# OpenPneu_ver2.net
KiCad netlist of a schematic drawn in EAGLE
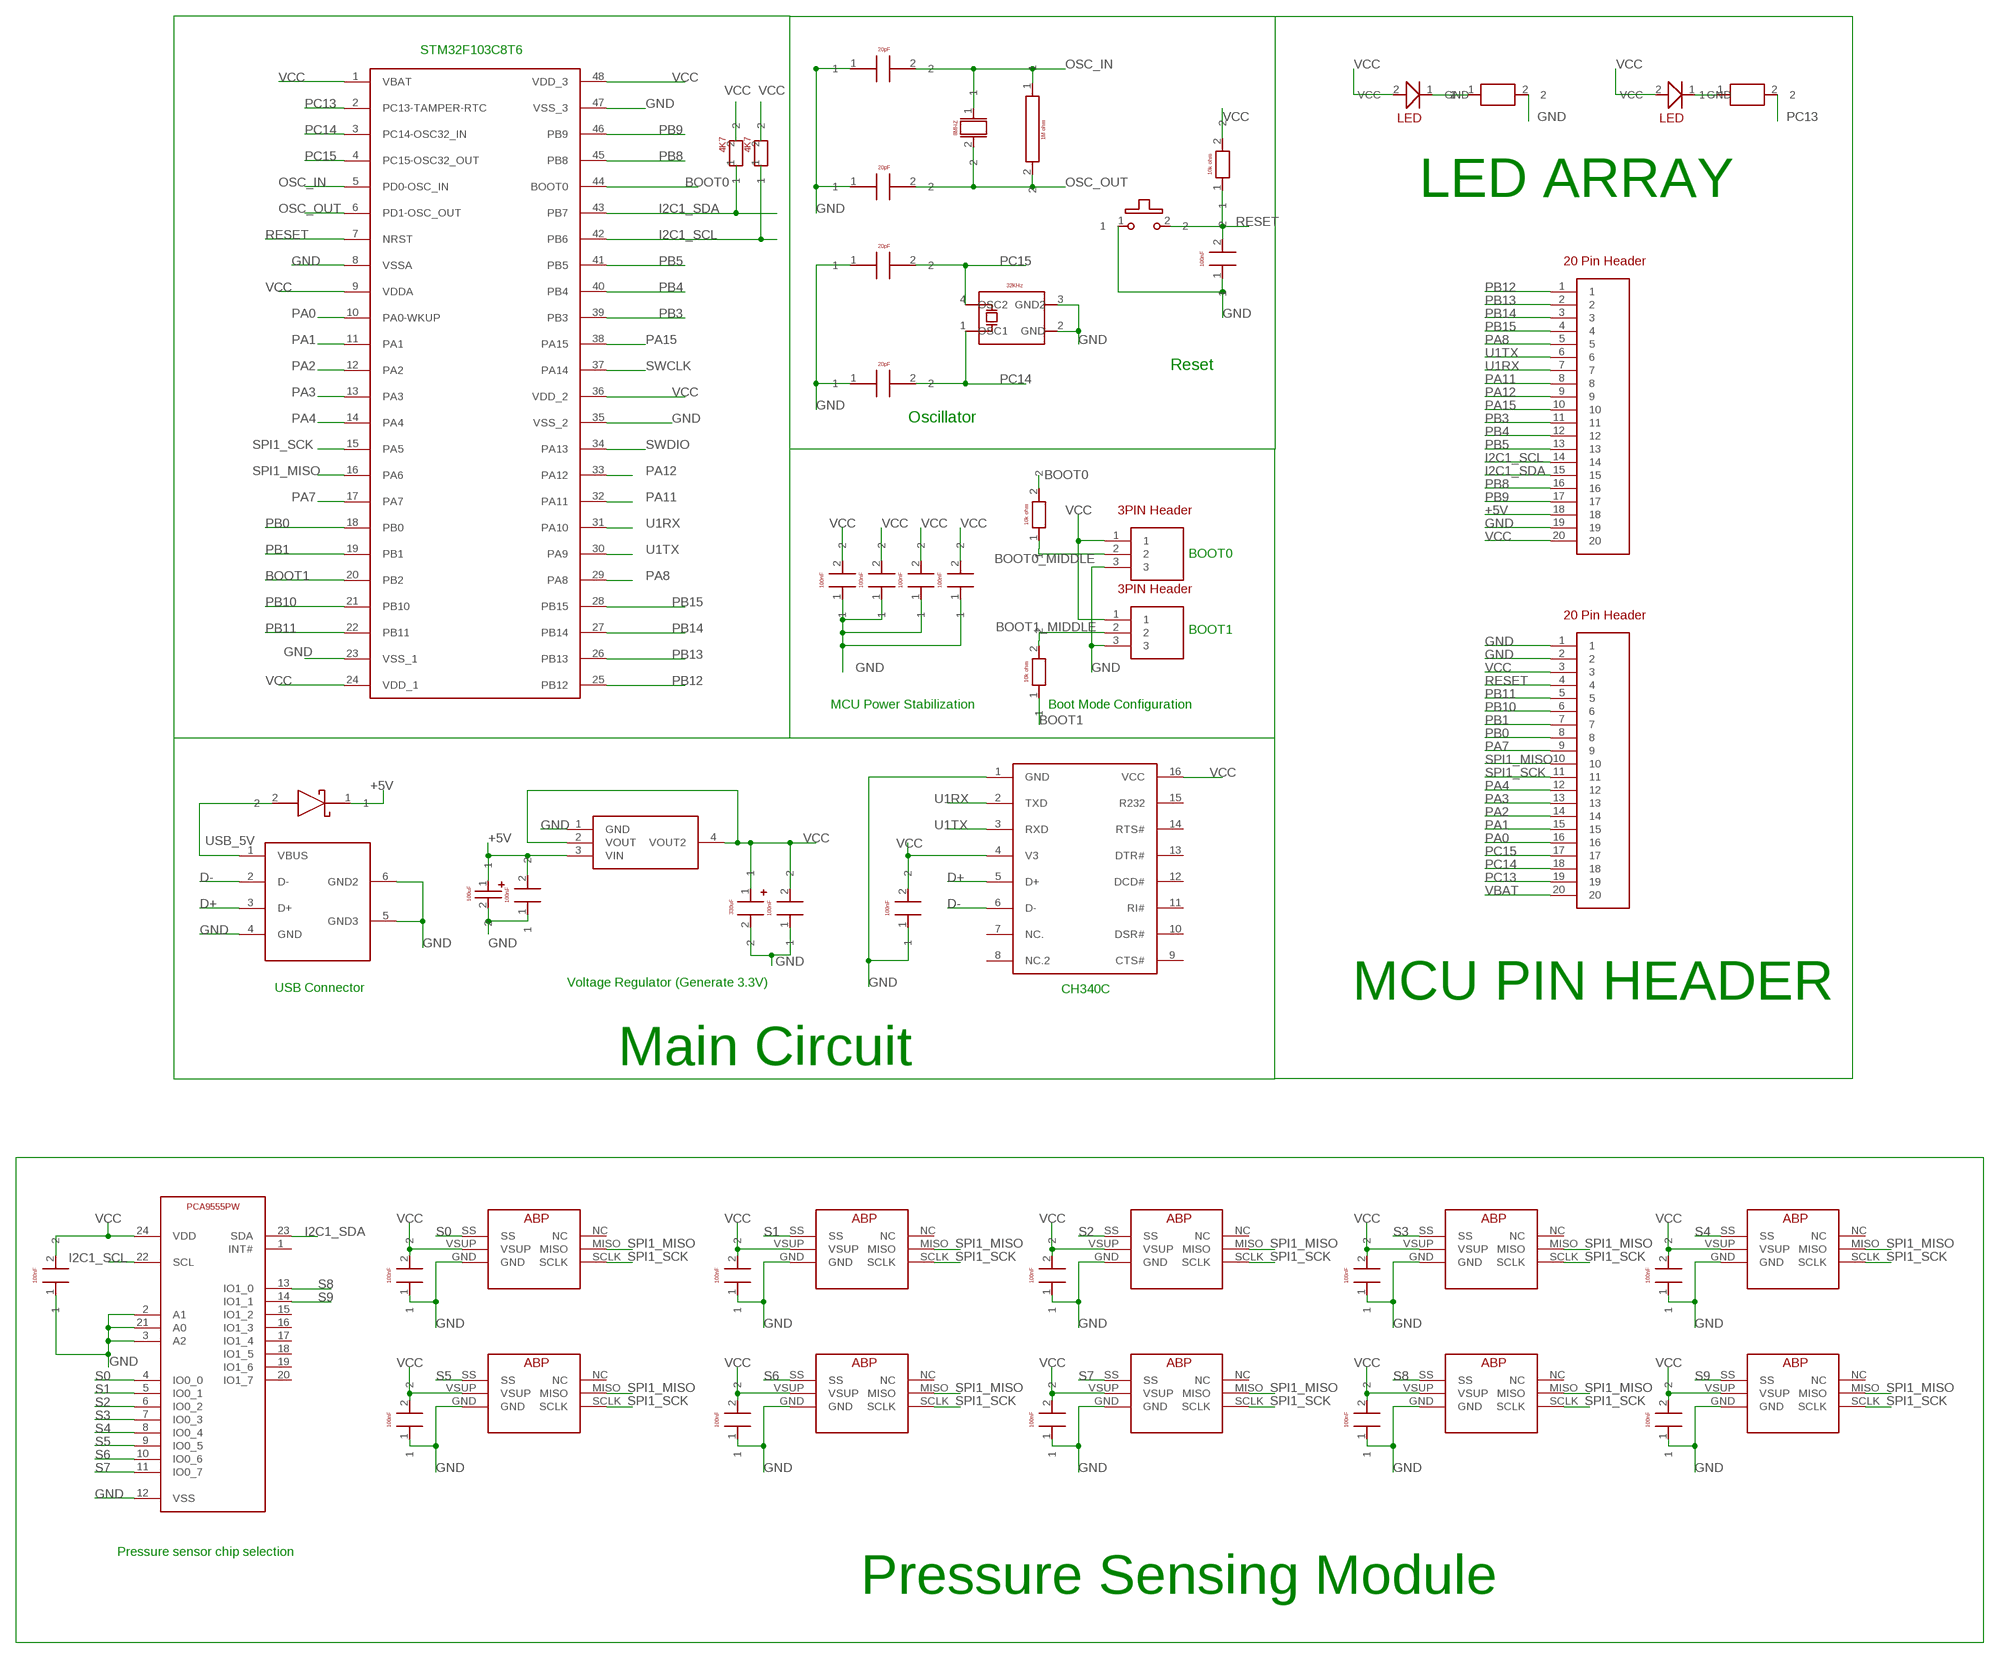
[diagram p0: schematic, sheet 1, part 1 of 3]
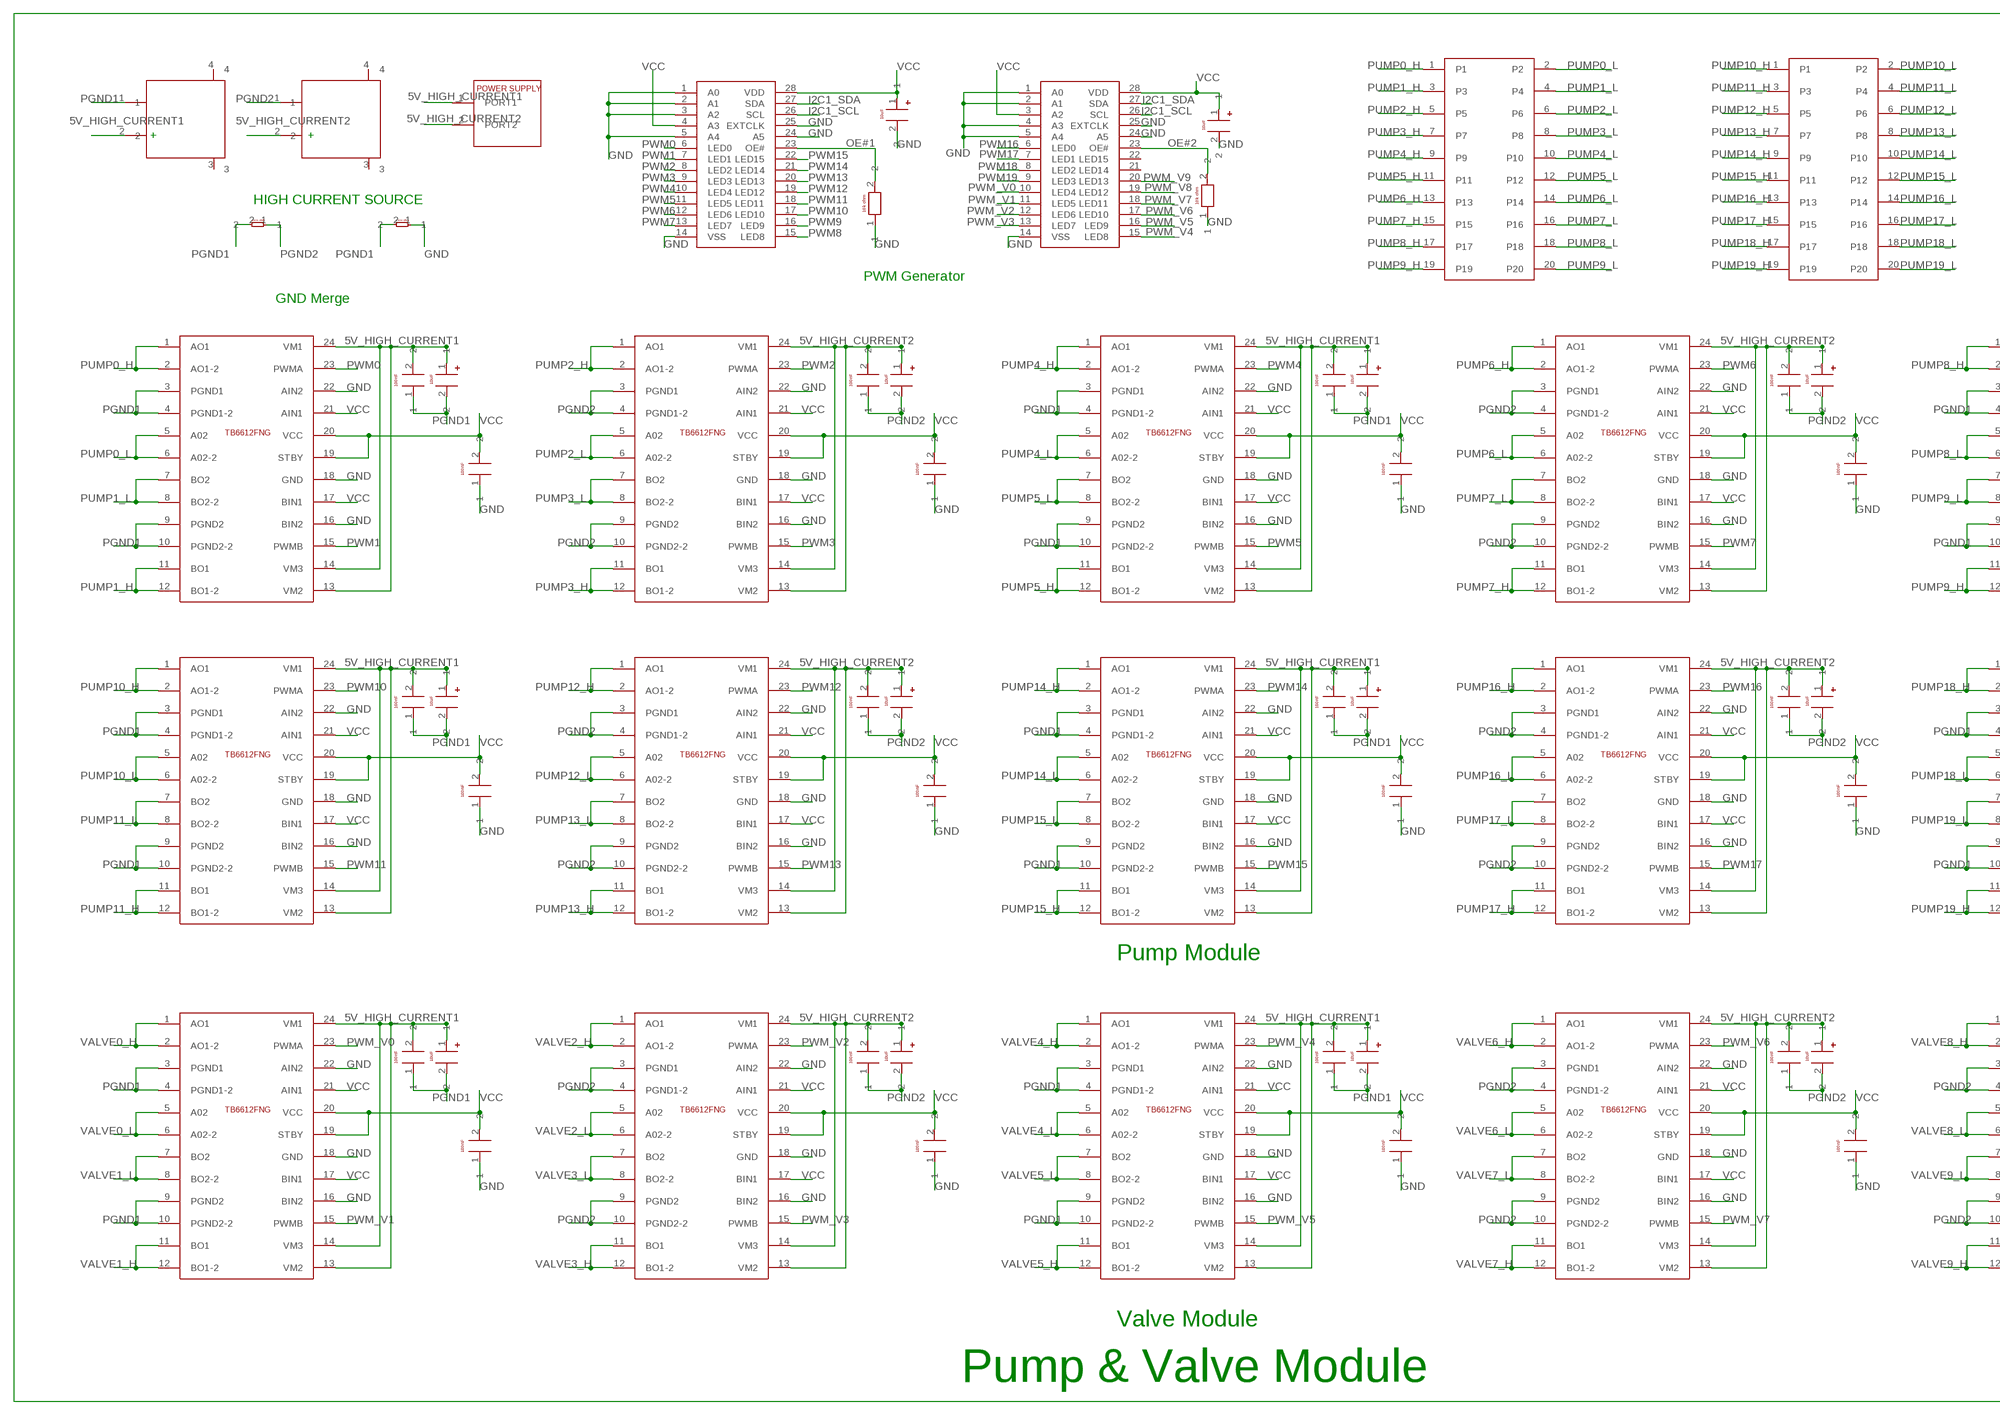
[diagram p1: schematic, sheet 1, part 2 of 3]
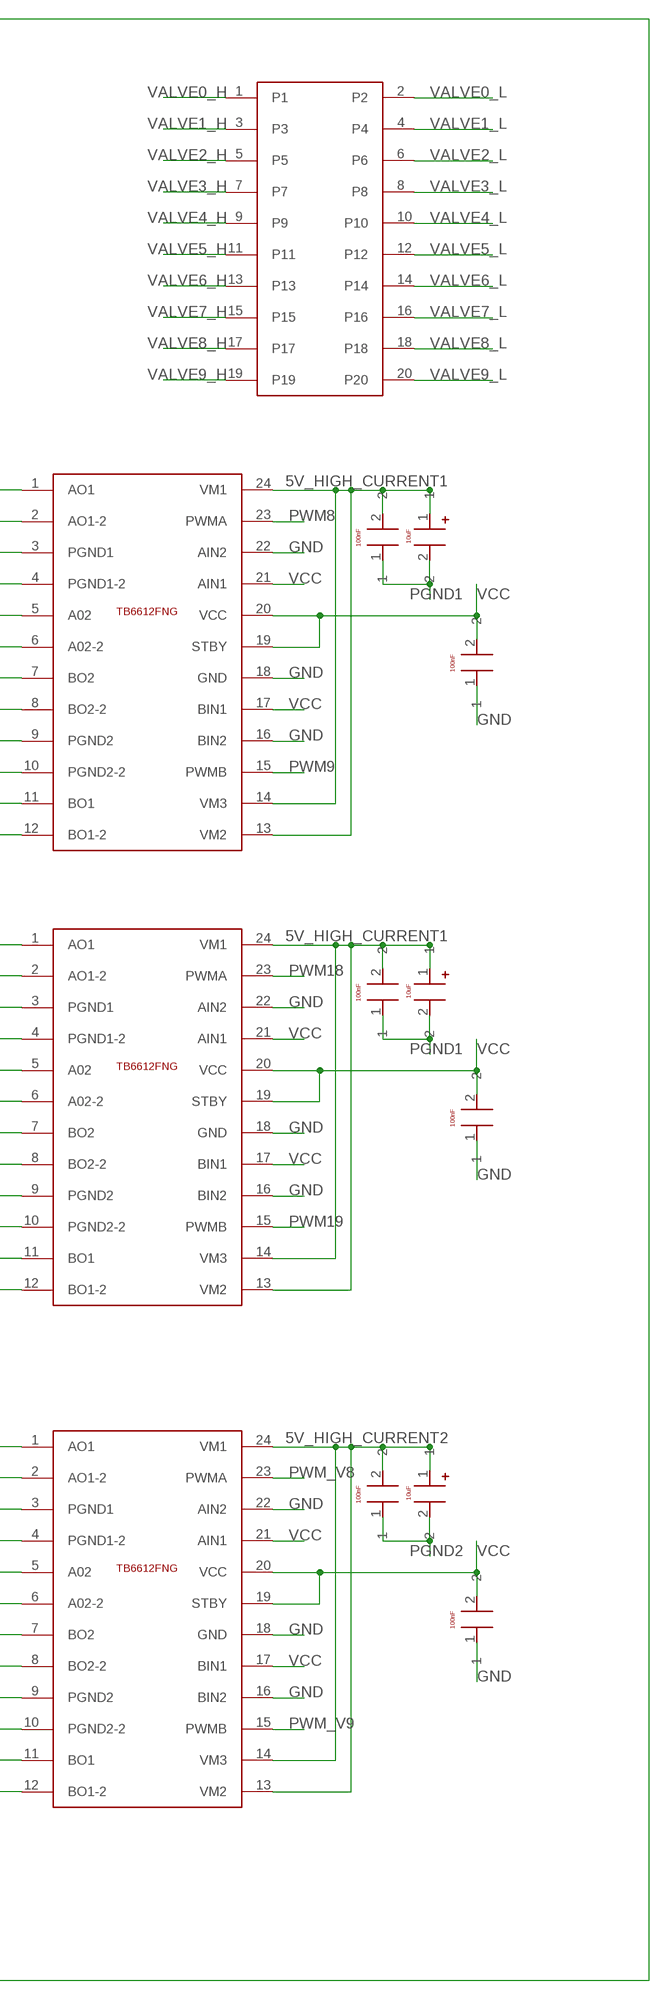
[diagram p2: schematic, sheet 1, part 3 of 3]

(export (version "E")
  (design (tool "Eeschema 10.0.6"))
  (components
    (comp (ref "J1")
      (value "D01-9922046")
      (footprint "eagle-import:HDRV20W46P0X254_1X20_5090X254X")
      (fields (field (name "RS_PART_NUMBER") "5473302"))
      (libsource (lib "eagle-import") (part "D01-9922046"))
    )
    (comp (ref "J2")
      (value "D01-9922046")
      (footprint "eagle-import:HDRV20W46P0X254_1X20_5090X254X")
      (fields (field (name "RS_PART_NUMBER") "5473302"))
      (libsource (lib "eagle-import") (part "D01-9922046"))
    )
    (comp (ref "U$1")
      (value "STM32F103_DEVICE")
      (footprint "eagle-import:LQFP-48_L7.0-W7.0-P0.50-LS9.27PRIMARY")
      (libsource (lib "eagle-import") (part "STM32F103_DEVICE"))
    )
    (comp (ref "U$2")
      (value "8MHZ_DEVICE")
      (footprint "eagle-import:CRYSTAL-SMD_L11.5-W4.8-LS12.A9PRIMARY")
      (libsource (lib "eagle-import") (part "8MHZ_DEVICE"))
    )
    (comp (ref "U$3")
      (value "20PF_DEVICE")
      (footprint "eagle-import:C0603_1PRIMARY")
      (libsource (lib "eagle-import") (part "20PF_DEVICE"))
    )
    (comp (ref "U$4")
      (value "20PF_DEVICE")
      (footprint "eagle-import:C0603_1PRIMARY")
      (libsource (lib "eagle-import") (part "20PF_DEVICE"))
    )
    (comp (ref "U$5")
      (value "1M_DEVICE")
      (footprint "eagle-import:R0603_1PRIMARY")
      (libsource (lib "eagle-import") (part "1M_DEVICE"))
    )
    (comp (ref "U$6")
      (value "32KHZ_DEVICE")
      (footprint "eagle-import:MC-306_4P-L8.0-W3.2-P5.5-BL_1PRIMARY")
      (libsource (lib "eagle-import") (part "32KHZ_DEVICE"))
    )
    (comp (ref "U$7")
      (value "20PF_DEVICE")
      (footprint "eagle-import:C0603_1PRIMARY")
      (libsource (lib "eagle-import") (part "20PF_DEVICE"))
    )
    (comp (ref "U$8")
      (value "20PF_DEVICE")
      (footprint "eagle-import:C0603_1PRIMARY")
      (libsource (lib "eagle-import") (part "20PF_DEVICE"))
    )
    (comp (ref "U$9")
      (value "VOLTAGE_REGULATOR")
      (footprint "eagle-import:SOT-223-3_L6.5-W3.4-P2.30-LS59PRIMARY")
      (libsource (lib "eagle-import") (part "VOLTAGE_REGULATOR"))
    )
    (comp (ref "U$10")
      (value "100UF")
      (footprint "eagle-import:CAP-SMD_L6.0-W3.2-R-RD_1PRIMARY")
      (libsource (lib "eagle-import") (part "100UF"))
    )
    (comp (ref "U$11")
      (value "100NF_DEVICE")
      (footprint "eagle-import:C0603_1PRIMARY")
      (libsource (lib "eagle-import") (part "100NF_DEVICE"))
    )
    (comp (ref "U$12")
      (value "330UF_DEVICE")
      (footprint "eagle-import:CAP-SMD_L6.0-W3.2-R-RD_1PRIMARY")
      (libsource (lib "eagle-import") (part "330UF_DEVICE"))
    )
    (comp (ref "U$13")
      (value "100NF_DEVICE")
      (footprint "eagle-import:C0603_1PRIMARY")
      (libsource (lib "eagle-import") (part "100NF_DEVICE"))
    )
    (comp (ref "U$14")
      (value "100NF_DEVICE")
      (footprint "eagle-import:C0603_1PRIMARY")
      (libsource (lib "eagle-import") (part "100NF_DEVICE"))
    )
    (comp (ref "U$15")
      (value "100NF_DEVICE")
      (footprint "eagle-import:C0603_1PRIMARY")
      (libsource (lib "eagle-import") (part "100NF_DEVICE"))
    )
    (comp (ref "U$16")
      (value "100NF_DEVICE")
      (footprint "eagle-import:C0603_1PRIMARY")
      (libsource (lib "eagle-import") (part "100NF_DEVICE"))
    )
    (comp (ref "U$17")
      (value "100NF_DEVICE")
      (footprint "eagle-import:C0603_1PRIMARY")
      (libsource (lib "eagle-import") (part "100NF_DEVICE"))
    )
    (comp (ref "U$18")
      (value "USB_NORM_VER2_DEV")
      (footprint "eagle-import:USB-B-TH_USB-B01_1PRIMARY")
      (libsource (lib "eagle-import") (part "USB_NORM_VER2_DEV"))
    )
    (comp (ref "U$19")
      (value "DIODE_DEVICE")
      (footprint "eagle-import:SMA_L4.4-W2.8-LS5.4-RD_1PRIMARY")
      (libsource (lib "eagle-import") (part "DIODE_DEVICE"))
    )
    (comp (ref "U$20")
      (value "CH340C_DEVICE")
      (footprint "eagle-import:SOP-16_L10.0-W3.9-P1.27-LS6.C7PRIMARY")
      (libsource (lib "eagle-import") (part "CH340C_DEVICE"))
    )
    (comp (ref "U$21")
      (value "100NF_DEVICE")
      (footprint "eagle-import:C0603_1PRIMARY")
      (libsource (lib "eagle-import") (part "100NF_DEVICE"))
    )
    (comp (ref "U$22")
      (value "3PIN_DEVICE")
      (footprint "eagle-import:HDRV20W46P0X254_1X20_5090X254X")
      (libsource (lib "eagle-import") (part "3PIN_DEVICE"))
    )
    (comp (ref "U$23")
      (value "3PIN_DEVICE")
      (footprint "eagle-import:HDRV20W46P0X254_1X20_5090X254X")
      (libsource (lib "eagle-import") (part "3PIN_DEVICE"))
    )
    (comp (ref "U$24")
      (value "10K_DEVICE")
      (footprint "eagle-import:R0603_1PRIMARY")
      (libsource (lib "eagle-import") (part "10K_DEVICE"))
    )
    (comp (ref "U$25")
      (value "10K_DEVICE")
      (footprint "eagle-import:R0603_1PRIMARY")
      (libsource (lib "eagle-import") (part "10K_DEVICE"))
    )
    (comp (ref "U$26")
      (value "BUTTON_DEVICE")
      (footprint "eagle-import:SW-SMD_SMK_JPM1040-XXXXFC_1PRIMARY")
      (libsource (lib "eagle-import") (part "BUTTON_DEVICE"))
    )
    (comp (ref "U$27")
      (value "POWER")
      (footprint "eagle-import:CONN-TH_P5.00_KF301-5.0-2P_1PRIMARY")
      (libsource (lib "eagle-import") (part "POWER"))
    )
    (comp (ref "U$28")
      (value "10K_DEVICE")
      (footprint "eagle-import:R0603_1PRIMARY")
      (libsource (lib "eagle-import") (part "10K_DEVICE"))
    )
    (comp (ref "U$29")
      (value "PCA9685PCA9685")
      (footprint "eagle-import:TSSOP-28_L9.7-W4.4-P0.65-LS6FFPRIMARY")
      (libsource (lib "eagle-import") (part "PCA9685PCA9685"))
    )
    (comp (ref "U$30")
      (value "PCA9685PCA9685")
      (footprint "eagle-import:TSSOP-28_L9.7-W4.4-P0.65-LS6FFPRIMARY")
      (libsource (lib "eagle-import") (part "PCA9685PCA9685"))
    )
    (comp (ref "U$31")
      (value "10K_DEVICE")
      (footprint "eagle-import:R0603_1PRIMARY")
      (libsource (lib "eagle-import") (part "10K_DEVICE"))
    )
    (comp (ref "U$32")
      (value "10UF_DEVICE")
      (footprint "eagle-import:CAP-SMD_L3.5-W2.8-R-RD_1PRIMARY")
      (libsource (lib "eagle-import") (part "10UF_DEVICE"))
    )
    (comp (ref "U$33")
      (value "10UF_DEVICE")
      (footprint "eagle-import:CAP-SMD_L3.5-W2.8-R-RD_1PRIMARY")
      (libsource (lib "eagle-import") (part "10UF_DEVICE"))
    )
    (comp (ref "U$34")
      (value "10K_DEVICE")
      (footprint "eagle-import:R0603_1PRIMARY")
      (libsource (lib "eagle-import") (part "10K_DEVICE"))
    )
    (comp (ref "U$35")
      (value "TB6612FNG")
      (footprint "eagle-import:SSOP-24_L8.3-W5.6-P0.65-LS7.93PRIMARY")
      (libsource (lib "eagle-import") (part "TB6612FNG"))
    )
    (comp (ref "U$36")
      (value "TB6612FNG")
      (footprint "eagle-import:SSOP-24_L8.3-W5.6-P0.65-LS7.93PRIMARY")
      (libsource (lib "eagle-import") (part "TB6612FNG"))
    )
    (comp (ref "U$37")
      (value "100NF_DEVICE")
      (footprint "eagle-import:C0603_1PRIMARY")
      (libsource (lib "eagle-import") (part "100NF_DEVICE"))
    )
    (comp (ref "U$38")
      (value "10UF_DEVICE")
      (footprint "eagle-import:CAP-SMD_L3.5-W2.8-R-RD_1PRIMARY")
      (libsource (lib "eagle-import") (part "10UF_DEVICE"))
    )
    (comp (ref "U$39")
      (value "100NF_DEVICE")
      (footprint "eagle-import:C0603_1PRIMARY")
      (libsource (lib "eagle-import") (part "100NF_DEVICE"))
    )
    (comp (ref "U$40")
      (value "100NF_DEVICE")
      (footprint "eagle-import:C0603_1PRIMARY")
      (libsource (lib "eagle-import") (part "100NF_DEVICE"))
    )
    (comp (ref "U$41")
      (value "10UF_DEVICE")
      (footprint "eagle-import:CAP-SMD_L3.5-W2.8-R-RD_1PRIMARY")
      (libsource (lib "eagle-import") (part "10UF_DEVICE"))
    )
    (comp (ref "U$42")
      (value "100NF_DEVICE")
      (footprint "eagle-import:C0603_1PRIMARY")
      (libsource (lib "eagle-import") (part "100NF_DEVICE"))
    )
    (comp (ref "U$43")
      (value "TB6612FNG")
      (footprint "eagle-import:SSOP-24_L8.3-W5.6-P0.65-LS7.93PRIMARY")
      (libsource (lib "eagle-import") (part "TB6612FNG"))
    )
    (comp (ref "U$44")
      (value "100NF_DEVICE")
      (footprint "eagle-import:C0603_1PRIMARY")
      (libsource (lib "eagle-import") (part "100NF_DEVICE"))
    )
    (comp (ref "U$45")
      (value "10UF_DEVICE")
      (footprint "eagle-import:CAP-SMD_L3.5-W2.8-R-RD_1PRIMARY")
      (libsource (lib "eagle-import") (part "10UF_DEVICE"))
    )
    (comp (ref "U$46")
      (value "100NF_DEVICE")
      (footprint "eagle-import:C0603_1PRIMARY")
      (libsource (lib "eagle-import") (part "100NF_DEVICE"))
    )
    (comp (ref "U$47")
      (value "TB6612FNG")
      (footprint "eagle-import:SSOP-24_L8.3-W5.6-P0.65-LS7.93PRIMARY")
      (libsource (lib "eagle-import") (part "TB6612FNG"))
    )
    (comp (ref "U$48")
      (value "100NF_DEVICE")
      (footprint "eagle-import:C0603_1PRIMARY")
      (libsource (lib "eagle-import") (part "100NF_DEVICE"))
    )
    (comp (ref "U$49")
      (value "10UF_DEVICE")
      (footprint "eagle-import:CAP-SMD_L3.5-W2.8-R-RD_1PRIMARY")
      (libsource (lib "eagle-import") (part "10UF_DEVICE"))
    )
    (comp (ref "U$50")
      (value "100NF_DEVICE")
      (footprint "eagle-import:C0603_1PRIMARY")
      (libsource (lib "eagle-import") (part "100NF_DEVICE"))
    )
    (comp (ref "U$51")
      (value "TB6612FNG")
      (footprint "eagle-import:SSOP-24_L8.3-W5.6-P0.65-LS7.93PRIMARY")
      (libsource (lib "eagle-import") (part "TB6612FNG"))
    )
    (comp (ref "U$52")
      (value "100NF_DEVICE")
      (footprint "eagle-import:C0603_1PRIMARY")
      (libsource (lib "eagle-import") (part "100NF_DEVICE"))
    )
    (comp (ref "U$53")
      (value "10UF_DEVICE")
      (footprint "eagle-import:CAP-SMD_L3.5-W2.8-R-RD_1PRIMARY")
      (libsource (lib "eagle-import") (part "10UF_DEVICE"))
    )
    (comp (ref "U$54")
      (value "100NF_DEVICE")
      (footprint "eagle-import:C0603_1PRIMARY")
      (libsource (lib "eagle-import") (part "100NF_DEVICE"))
    )
    (comp (ref "U$55")
      (value "TB6612FNG")
      (footprint "eagle-import:SSOP-24_L8.3-W5.6-P0.65-LS7.93PRIMARY")
      (libsource (lib "eagle-import") (part "TB6612FNG"))
    )
    (comp (ref "U$56")
      (value "100NF_DEVICE")
      (footprint "eagle-import:C0603_1PRIMARY")
      (libsource (lib "eagle-import") (part "100NF_DEVICE"))
    )
    (comp (ref "U$57")
      (value "10UF_DEVICE")
      (footprint "eagle-import:CAP-SMD_L3.5-W2.8-R-RD_1PRIMARY")
      (libsource (lib "eagle-import") (part "10UF_DEVICE"))
    )
    (comp (ref "U$58")
      (value "100NF_DEVICE")
      (footprint "eagle-import:C0603_1PRIMARY")
      (libsource (lib "eagle-import") (part "100NF_DEVICE"))
    )
    (comp (ref "U$59")
      (value "TB6612FNG")
      (footprint "eagle-import:SSOP-24_L8.3-W5.6-P0.65-LS7.93PRIMARY")
      (libsource (lib "eagle-import") (part "TB6612FNG"))
    )
    (comp (ref "U$60")
      (value "100NF_DEVICE")
      (footprint "eagle-import:C0603_1PRIMARY")
      (libsource (lib "eagle-import") (part "100NF_DEVICE"))
    )
    (comp (ref "U$61")
      (value "10UF_DEVICE")
      (footprint "eagle-import:CAP-SMD_L3.5-W2.8-R-RD_1PRIMARY")
      (libsource (lib "eagle-import") (part "10UF_DEVICE"))
    )
    (comp (ref "U$62")
      (value "100NF_DEVICE")
      (footprint "eagle-import:C0603_1PRIMARY")
      (libsource (lib "eagle-import") (part "100NF_DEVICE"))
    )
    (comp (ref "U$63")
      (value "TB6612FNG")
      (footprint "eagle-import:SSOP-24_L8.3-W5.6-P0.65-LS7.93PRIMARY")
      (libsource (lib "eagle-import") (part "TB6612FNG"))
    )
    (comp (ref "U$64")
      (value "100NF_DEVICE")
      (footprint "eagle-import:C0603_1PRIMARY")
      (libsource (lib "eagle-import") (part "100NF_DEVICE"))
    )
    (comp (ref "U$65")
      (value "10UF_DEVICE")
      (footprint "eagle-import:CAP-SMD_L3.5-W2.8-R-RD_1PRIMARY")
      (libsource (lib "eagle-import") (part "10UF_DEVICE"))
    )
    (comp (ref "U$66")
      (value "100NF_DEVICE")
      (footprint "eagle-import:C0603_1PRIMARY")
      (libsource (lib "eagle-import") (part "100NF_DEVICE"))
    )
    (comp (ref "U$67")
      (value "TB6612FNG")
      (footprint "eagle-import:SSOP-24_L8.3-W5.6-P0.65-LS7.93PRIMARY")
      (libsource (lib "eagle-import") (part "TB6612FNG"))
    )
    (comp (ref "U$68")
      (value "100NF_DEVICE")
      (footprint "eagle-import:C0603_1PRIMARY")
      (libsource (lib "eagle-import") (part "100NF_DEVICE"))
    )
    (comp (ref "U$69")
      (value "10UF_DEVICE")
      (footprint "eagle-import:CAP-SMD_L3.5-W2.8-R-RD_1PRIMARY")
      (libsource (lib "eagle-import") (part "10UF_DEVICE"))
    )
    (comp (ref "U$70")
      (value "100NF_DEVICE")
      (footprint "eagle-import:C0603_1PRIMARY")
      (libsource (lib "eagle-import") (part "100NF_DEVICE"))
    )
    (comp (ref "U$71")
      (value "TB6612FNG")
      (footprint "eagle-import:SSOP-24_L8.3-W5.6-P0.65-LS7.93PRIMARY")
      (libsource (lib "eagle-import") (part "TB6612FNG"))
    )
    (comp (ref "U$72")
      (value "100NF_DEVICE")
      (footprint "eagle-import:C0603_1PRIMARY")
      (libsource (lib "eagle-import") (part "100NF_DEVICE"))
    )
    (comp (ref "U$73")
      (value "10UF_DEVICE")
      (footprint "eagle-import:CAP-SMD_L3.5-W2.8-R-RD_1PRIMARY")
      (libsource (lib "eagle-import") (part "10UF_DEVICE"))
    )
    (comp (ref "U$74")
      (value "100NF_DEVICE")
      (footprint "eagle-import:C0603_1PRIMARY")
      (libsource (lib "eagle-import") (part "100NF_DEVICE"))
    )
    (comp (ref "U$75")
      (value "TB6612FNG")
      (footprint "eagle-import:SSOP-24_L8.3-W5.6-P0.65-LS7.93PRIMARY")
      (libsource (lib "eagle-import") (part "TB6612FNG"))
    )
    (comp (ref "U$76")
      (value "100NF_DEVICE")
      (footprint "eagle-import:C0603_1PRIMARY")
      (libsource (lib "eagle-import") (part "100NF_DEVICE"))
    )
    (comp (ref "U$77")
      (value "10UF_DEVICE")
      (footprint "eagle-import:CAP-SMD_L3.5-W2.8-R-RD_1PRIMARY")
      (libsource (lib "eagle-import") (part "10UF_DEVICE"))
    )
    (comp (ref "U$78")
      (value "100NF_DEVICE")
      (footprint "eagle-import:C0603_1PRIMARY")
      (libsource (lib "eagle-import") (part "100NF_DEVICE"))
    )
    (comp (ref "U$79")
      (value "TB6612FNG")
      (footprint "eagle-import:SSOP-24_L8.3-W5.6-P0.65-LS7.93PRIMARY")
      (libsource (lib "eagle-import") (part "TB6612FNG"))
    )
    (comp (ref "U$80")
      (value "100NF_DEVICE")
      (footprint "eagle-import:C0603_1PRIMARY")
      (libsource (lib "eagle-import") (part "100NF_DEVICE"))
    )
    (comp (ref "U$81")
      (value "10UF_DEVICE")
      (footprint "eagle-import:CAP-SMD_L3.5-W2.8-R-RD_1PRIMARY")
      (libsource (lib "eagle-import") (part "10UF_DEVICE"))
    )
    (comp (ref "U$82")
      (value "100NF_DEVICE")
      (footprint "eagle-import:C0603_1PRIMARY")
      (libsource (lib "eagle-import") (part "100NF_DEVICE"))
    )
    (comp (ref "U$83")
      (value "TB6612FNG")
      (footprint "eagle-import:SSOP-24_L8.3-W5.6-P0.65-LS7.93PRIMARY")
      (libsource (lib "eagle-import") (part "TB6612FNG"))
    )
    (comp (ref "U$84")
      (value "100NF_DEVICE")
      (footprint "eagle-import:C0603_1PRIMARY")
      (libsource (lib "eagle-import") (part "100NF_DEVICE"))
    )
    (comp (ref "U$85")
      (value "10UF_DEVICE")
      (footprint "eagle-import:CAP-SMD_L3.5-W2.8-R-RD_1PRIMARY")
      (libsource (lib "eagle-import") (part "10UF_DEVICE"))
    )
    (comp (ref "U$86")
      (value "100NF_DEVICE")
      (footprint "eagle-import:C0603_1PRIMARY")
      (libsource (lib "eagle-import") (part "100NF_DEVICE"))
    )
    (comp (ref "U$87")
      (value "TB6612FNG")
      (footprint "eagle-import:SSOP-24_L8.3-W5.6-P0.65-LS7.93PRIMARY")
      (libsource (lib "eagle-import") (part "TB6612FNG"))
    )
    (comp (ref "U$88")
      (value "100NF_DEVICE")
      (footprint "eagle-import:C0603_1PRIMARY")
      (libsource (lib "eagle-import") (part "100NF_DEVICE"))
    )
    (comp (ref "U$89")
      (value "10UF_DEVICE")
      (footprint "eagle-import:CAP-SMD_L3.5-W2.8-R-RD_1PRIMARY")
      (libsource (lib "eagle-import") (part "10UF_DEVICE"))
    )
    (comp (ref "U$90")
      (value "100NF_DEVICE")
      (footprint "eagle-import:C0603_1PRIMARY")
      (libsource (lib "eagle-import") (part "100NF_DEVICE"))
    )
    (comp (ref "U$91")
      (value "TB6612FNG")
      (footprint "eagle-import:SSOP-24_L8.3-W5.6-P0.65-LS7.93PRIMARY")
      (libsource (lib "eagle-import") (part "TB6612FNG"))
    )
    (comp (ref "U$92")
      (value "100NF_DEVICE")
      (footprint "eagle-import:C0603_1PRIMARY")
      (libsource (lib "eagle-import") (part "100NF_DEVICE"))
    )
    (comp (ref "U$93")
      (value "10UF_DEVICE")
      (footprint "eagle-import:CAP-SMD_L3.5-W2.8-R-RD_1PRIMARY")
      (libsource (lib "eagle-import") (part "10UF_DEVICE"))
    )
    (comp (ref "U$94")
      (value "100NF_DEVICE")
      (footprint "eagle-import:C0603_1PRIMARY")
      (libsource (lib "eagle-import") (part "100NF_DEVICE"))
    )
    (comp (ref "U$95")
      (value "ABPDANN1.6BGSA")
      (footprint "eagle-import:ABPDANN1.6BGSA")
      (libsource (lib "eagle-import") (part "ABPDANN1.6BGSA"))
    )
    (comp (ref "U$96")
      (value "ABPDANN1.6BGSA")
      (footprint "eagle-import:ABPDANN1.6BGSA")
      (libsource (lib "eagle-import") (part "ABPDANN1.6BGSA"))
    )
    (comp (ref "U$97")
      (value "100NF_DEVICE")
      (footprint "eagle-import:C0603_1PRIMARY")
      (libsource (lib "eagle-import") (part "100NF_DEVICE"))
    )
    (comp (ref "U$98")
      (value "100NF_DEVICE")
      (footprint "eagle-import:C0603_1PRIMARY")
      (libsource (lib "eagle-import") (part "100NF_DEVICE"))
    )
    (comp (ref "U$99")
      (value "ABPDANN1.6BGSA")
      (footprint "eagle-import:ABPDANN1.6BGSA")
      (libsource (lib "eagle-import") (part "ABPDANN1.6BGSA"))
    )
    (comp (ref "U$100")
      (value "100NF_DEVICE")
      (footprint "eagle-import:C0603_1PRIMARY")
      (libsource (lib "eagle-import") (part "100NF_DEVICE"))
    )
    (comp (ref "U$101")
      (value "ABPDANN1.6BGSA")
      (footprint "eagle-import:ABPDANN1.6BGSA")
      (libsource (lib "eagle-import") (part "ABPDANN1.6BGSA"))
    )
    (comp (ref "U$102")
      (value "100NF_DEVICE")
      (footprint "eagle-import:C0603_1PRIMARY")
      (libsource (lib "eagle-import") (part "100NF_DEVICE"))
    )
    (comp (ref "U$103")
      (value "ABPDANN1.6BGSA")
      (footprint "eagle-import:ABPDANN1.6BGSA")
      (libsource (lib "eagle-import") (part "ABPDANN1.6BGSA"))
    )
    (comp (ref "U$104")
      (value "100NF_DEVICE")
      (footprint "eagle-import:C0603_1PRIMARY")
      (libsource (lib "eagle-import") (part "100NF_DEVICE"))
    )
    (comp (ref "U$105")
      (value "ABPDANN1.6BGSA")
      (footprint "eagle-import:ABPDANN1.6BGSA")
      (libsource (lib "eagle-import") (part "ABPDANN1.6BGSA"))
    )
    (comp (ref "U$106")
      (value "100NF_DEVICE")
      (footprint "eagle-import:C0603_1PRIMARY")
      (libsource (lib "eagle-import") (part "100NF_DEVICE"))
    )
    (comp (ref "U$107")
      (value "ABPDANN1.6BGSA")
      (footprint "eagle-import:ABPDANN1.6BGSA")
      (libsource (lib "eagle-import") (part "ABPDANN1.6BGSA"))
    )
    (comp (ref "U$108")
      (value "100NF_DEVICE")
      (footprint "eagle-import:C0603_1PRIMARY")
      (libsource (lib "eagle-import") (part "100NF_DEVICE"))
    )
    (comp (ref "U$109")
      (value "ABPDANN1.6BGSA")
      (footprint "eagle-import:ABPDANN1.6BGSA")
      (libsource (lib "eagle-import") (part "ABPDANN1.6BGSA"))
    )
    (comp (ref "U$110")
      (value "100NF_DEVICE")
      (footprint "eagle-import:C0603_1PRIMARY")
      (libsource (lib "eagle-import") (part "100NF_DEVICE"))
    )
    (comp (ref "U$111")
      (value "ABPDANN1.6BGSA")
      (footprint "eagle-import:ABPDANN1.6BGSA")
      (libsource (lib "eagle-import") (part "ABPDANN1.6BGSA"))
    )
    (comp (ref "U$112")
      (value "100NF_DEVICE")
      (footprint "eagle-import:C0603_1PRIMARY")
      (libsource (lib "eagle-import") (part "100NF_DEVICE"))
    )
    (comp (ref "U$113")
      (value "ABPDANN1.6BGSA")
      (footprint "eagle-import:ABPDANN1.6BGSA")
      (libsource (lib "eagle-import") (part "ABPDANN1.6BGSA"))
    )
    (comp (ref "U$114")
      (value "100NF_DEVICE")
      (footprint "eagle-import:C0603_1PRIMARY")
      (libsource (lib "eagle-import") (part "100NF_DEVICE"))
    )
    (comp (ref "U$115")
      (value "TSSOP-24_L7.8-W4.4-P0.65-LS652")
      (footprint "eagle-import:TSSOP-24_L7.8-W4.4-P0.65-LS652PRIMARY")
      (libsource (lib "eagle-import") (part "TSSOP-24_L7.8-W4.4-P0.65-LS652"))
    )
    (comp (ref "U$116")
      (value "100NF_DEVICE")
      (footprint "eagle-import:C0603_1PRIMARY")
      (libsource (lib "eagle-import") (part "100NF_DEVICE"))
    )
    (comp (ref "U$117")
      (value "XT60_DEVICE")
      (footprint "eagle-import:CONN-TH_XT60PW-M_1PRIMARY")
      (libsource (lib "eagle-import") (part "XT60_DEVICE"))
    )
    (comp (ref "U$118")
      (value "XT60_DEVICE")
      (footprint "eagle-import:CONN-TH_XT60PW-M_1PRIMARY")
      (libsource (lib "eagle-import") (part "XT60_DEVICE"))
    )
    (comp (ref "U$119")
      (value "ZERO_OHM")
      (footprint "eagle-import:ZERO_OHM_FOOT")
      (libsource (lib "eagle-import") (part "ZERO_OHM"))
    )
    (comp (ref "U$120")
      (value "ZERO_OHM")
      (footprint "eagle-import:ZERO_OHM_FOOT")
      (libsource (lib "eagle-import") (part "ZERO_OHM"))
    )
    (comp (ref "U$121")
      (value "PHB-2-10")
      (footprint "eagle-import:CONN-TH_PHB-2-10A_1PRIMARY")
      (libsource (lib "eagle-import") (part "PHB-2-10"))
    )
    (comp (ref "U$122")
      (value "PHB-2-10")
      (footprint "eagle-import:CONN-TH_PHB-2-10A_1PRIMARY")
      (libsource (lib "eagle-import") (part "PHB-2-10"))
    )
    (comp (ref "U$123")
      (value "PHB-2-10")
      (footprint "eagle-import:CONN-TH_PHB-2-10A_1PRIMARY")
      (libsource (lib "eagle-import") (part "PHB-2-10"))
    )
    (comp (ref "U$124")
      (value "LED")
      (footprint "eagle-import:LED0603-RD_1PRIMARY")
      (libsource (lib "eagle-import") (part "LED"))
    )
    (comp (ref "U$125")
      (value "LED")
      (footprint "eagle-import:LED0603-RD_1PRIMARY")
      (libsource (lib "eagle-import") (part "LED"))
    )
    (comp (ref "U$126")
      (value "510_OHM_DEVICE")
      (footprint "eagle-import:R0603_1PRIMARY")
      (libsource (lib "eagle-import") (part "510_OHM_DEVICE"))
    )
    (comp (ref "U$127")
      (value "510_OHM_DEVICE")
      (footprint "eagle-import:R0603_1PRIMARY")
      (libsource (lib "eagle-import") (part "510_OHM_DEVICE"))
    )
    (comp (ref "U$128")
      (value "4K7")
      (footprint "eagle-import:4K7")
      (libsource (lib "eagle-import") (part "4K7"))
    )
    (comp (ref "U$129")
      (value "4K7")
      (footprint "eagle-import:4K7")
      (libsource (lib "eagle-import") (part "4K7"))
    )
    (comp (ref "U$130")
      (value "100NF_DEVICE")
      (footprint "eagle-import:C0603_1PRIMARY")
      (libsource (lib "eagle-import") (part "100NF_DEVICE"))
    )
  )
  (nets
    (net (code "1") (name "/+5V") (class "Default")
      (node (ref "J1") (pin "18") (pinfunction "18_18") (pintype "bidirectional"))
      (node (ref "U$10") (pin "1") (pinfunction "1_1") (pintype "bidirectional"))
      (node (ref "U$11") (pin "2") (pinfunction "2_2") (pintype "bidirectional"))
      (node (ref "U$19") (pin "1") (pinfunction "1_1") (pintype "bidirectional"))
      (node (ref "U$9") (pin "3") (pinfunction "VIN_3") (pintype "bidirectional"))
    )
    (net (code "2") (name "/5V_HIGH_CURRENT1") (class "Default")
      (node (ref "U$117") (pin "2") (pinfunction "2_2") (pintype "bidirectional"))
      (node (ref "U$27") (pin "1") (pinfunction "PORT1_1") (pintype "bidirectional"))
      (node (ref "U$35") (pin "13") (pinfunction "VM2_13") (pintype "bidirectional"))
      (node (ref "U$35") (pin "14") (pinfunction "VM3_14") (pintype "bidirectional"))
      (node (ref "U$35") (pin "24") (pinfunction "VM1_24") (pintype "bidirectional"))
      (node (ref "U$37") (pin "2") (pinfunction "2_2") (pintype "bidirectional"))
      (node (ref "U$38") (pin "1") (pinfunction "1_1") (pintype "bidirectional"))
      (node (ref "U$43") (pin "13") (pinfunction "VM2_13") (pintype "bidirectional"))
      (node (ref "U$43") (pin "14") (pinfunction "VM3_14") (pintype "bidirectional"))
      (node (ref "U$43") (pin "24") (pinfunction "VM1_24") (pintype "bidirectional"))
      (node (ref "U$44") (pin "2") (pinfunction "2_2") (pintype "bidirectional"))
      (node (ref "U$45") (pin "1") (pinfunction "1_1") (pintype "bidirectional"))
      (node (ref "U$51") (pin "13") (pinfunction "VM2_13") (pintype "bidirectional"))
      (node (ref "U$51") (pin "14") (pinfunction "VM3_14") (pintype "bidirectional"))
      (node (ref "U$51") (pin "24") (pinfunction "VM1_24") (pintype "bidirectional"))
      (node (ref "U$52") (pin "2") (pinfunction "2_2") (pintype "bidirectional"))
      (node (ref "U$53") (pin "1") (pinfunction "1_1") (pintype "bidirectional"))
      (node (ref "U$55") (pin "13") (pinfunction "VM2_13") (pintype "bidirectional"))
      (node (ref "U$55") (pin "14") (pinfunction "VM3_14") (pintype "bidirectional"))
      (node (ref "U$55") (pin "24") (pinfunction "VM1_24") (pintype "bidirectional"))
      (node (ref "U$56") (pin "2") (pinfunction "2_2") (pintype "bidirectional"))
      (node (ref "U$57") (pin "1") (pinfunction "1_1") (pintype "bidirectional"))
      (node (ref "U$63") (pin "13") (pinfunction "VM2_13") (pintype "bidirectional"))
      (node (ref "U$63") (pin "14") (pinfunction "VM3_14") (pintype "bidirectional"))
      (node (ref "U$63") (pin "24") (pinfunction "VM1_24") (pintype "bidirectional"))
      (node (ref "U$64") (pin "2") (pinfunction "2_2") (pintype "bidirectional"))
      (node (ref "U$65") (pin "1") (pinfunction "1_1") (pintype "bidirectional"))
      (node (ref "U$71") (pin "13") (pinfunction "VM2_13") (pintype "bidirectional"))
      (node (ref "U$71") (pin "14") (pinfunction "VM3_14") (pintype "bidirectional"))
      (node (ref "U$71") (pin "24") (pinfunction "VM1_24") (pintype "bidirectional"))
      (node (ref "U$72") (pin "2") (pinfunction "2_2") (pintype "bidirectional"))
      (node (ref "U$73") (pin "1") (pinfunction "1_1") (pintype "bidirectional"))
      (node (ref "U$75") (pin "13") (pinfunction "VM2_13") (pintype "bidirectional"))
      (node (ref "U$75") (pin "14") (pinfunction "VM3_14") (pintype "bidirectional"))
      (node (ref "U$75") (pin "24") (pinfunction "VM1_24") (pintype "bidirectional"))
      (node (ref "U$76") (pin "2") (pinfunction "2_2") (pintype "bidirectional"))
      (node (ref "U$77") (pin "1") (pinfunction "1_1") (pintype "bidirectional"))
      (node (ref "U$83") (pin "13") (pinfunction "VM2_13") (pintype "bidirectional"))
      (node (ref "U$83") (pin "14") (pinfunction "VM3_14") (pintype "bidirectional"))
      (node (ref "U$83") (pin "24") (pinfunction "VM1_24") (pintype "bidirectional"))
      (node (ref "U$84") (pin "2") (pinfunction "2_2") (pintype "bidirectional"))
      (node (ref "U$85") (pin "1") (pinfunction "1_1") (pintype "bidirectional"))
    )
    (net (code "3") (name "/5V_HIGH_CURRENT2") (class "Default")
      (node (ref "U$118") (pin "2") (pinfunction "2_2") (pintype "bidirectional"))
      (node (ref "U$27") (pin "2") (pinfunction "PORT2_2") (pintype "bidirectional"))
      (node (ref "U$36") (pin "13") (pinfunction "VM2_13") (pintype "bidirectional"))
      (node (ref "U$36") (pin "14") (pinfunction "VM3_14") (pintype "bidirectional"))
      (node (ref "U$36") (pin "24") (pinfunction "VM1_24") (pintype "bidirectional"))
      (node (ref "U$40") (pin "2") (pinfunction "2_2") (pintype "bidirectional"))
      (node (ref "U$41") (pin "1") (pinfunction "1_1") (pintype "bidirectional"))
      (node (ref "U$47") (pin "13") (pinfunction "VM2_13") (pintype "bidirectional"))
      (node (ref "U$47") (pin "14") (pinfunction "VM3_14") (pintype "bidirectional"))
      (node (ref "U$47") (pin "24") (pinfunction "VM1_24") (pintype "bidirectional"))
      (node (ref "U$48") (pin "2") (pinfunction "2_2") (pintype "bidirectional"))
      (node (ref "U$49") (pin "1") (pinfunction "1_1") (pintype "bidirectional"))
      (node (ref "U$59") (pin "13") (pinfunction "VM2_13") (pintype "bidirectional"))
      (node (ref "U$59") (pin "14") (pinfunction "VM3_14") (pintype "bidirectional"))
      (node (ref "U$59") (pin "24") (pinfunction "VM1_24") (pintype "bidirectional"))
      (node (ref "U$60") (pin "2") (pinfunction "2_2") (pintype "bidirectional"))
      (node (ref "U$61") (pin "1") (pinfunction "1_1") (pintype "bidirectional"))
      (node (ref "U$67") (pin "13") (pinfunction "VM2_13") (pintype "bidirectional"))
      (node (ref "U$67") (pin "14") (pinfunction "VM3_14") (pintype "bidirectional"))
      (node (ref "U$67") (pin "24") (pinfunction "VM1_24") (pintype "bidirectional"))
      (node (ref "U$68") (pin "2") (pinfunction "2_2") (pintype "bidirectional"))
      (node (ref "U$69") (pin "1") (pinfunction "1_1") (pintype "bidirectional"))
      (node (ref "U$79") (pin "13") (pinfunction "VM2_13") (pintype "bidirectional"))
      (node (ref "U$79") (pin "14") (pinfunction "VM3_14") (pintype "bidirectional"))
      (node (ref "U$79") (pin "24") (pinfunction "VM1_24") (pintype "bidirectional"))
      (node (ref "U$80") (pin "2") (pinfunction "2_2") (pintype "bidirectional"))
      (node (ref "U$81") (pin "1") (pinfunction "1_1") (pintype "bidirectional"))
      (node (ref "U$87") (pin "13") (pinfunction "VM2_13") (pintype "bidirectional"))
      (node (ref "U$87") (pin "14") (pinfunction "VM3_14") (pintype "bidirectional"))
      (node (ref "U$87") (pin "24") (pinfunction "VM1_24") (pintype "bidirectional"))
      (node (ref "U$88") (pin "2") (pinfunction "2_2") (pintype "bidirectional"))
      (node (ref "U$89") (pin "1") (pinfunction "1_1") (pintype "bidirectional"))
      (node (ref "U$91") (pin "13") (pinfunction "VM2_13") (pintype "bidirectional"))
      (node (ref "U$91") (pin "14") (pinfunction "VM3_14") (pintype "bidirectional"))
      (node (ref "U$91") (pin "24") (pinfunction "VM1_24") (pintype "bidirectional"))
      (node (ref "U$92") (pin "2") (pinfunction "2_2") (pintype "bidirectional"))
      (node (ref "U$93") (pin "1") (pinfunction "1_1") (pintype "bidirectional"))
    )
    (net (code "4") (name "/BOOT0") (class "Default")
      (node (ref "U$1") (pin "44") (pinfunction "BOOT0_44") (pintype "bidirectional"))
      (node (ref "U$24") (pin "2") (pinfunction "2_2") (pintype "bidirectional"))
    )
    (net (code "5") (name "/BOOT0_MIDDLE") (class "Default")
      (node (ref "U$22") (pin "2") (pinfunction "2_2") (pintype "bidirectional"))
      (node (ref "U$24") (pin "1") (pinfunction "1_1") (pintype "bidirectional"))
    )
    (net (code "6") (name "/BOOT1") (class "Default")
      (node (ref "U$1") (pin "20") (pinfunction "PB2_20") (pintype "bidirectional"))
      (node (ref "U$25") (pin "1") (pinfunction "1_1") (pintype "bidirectional"))
    )
    (net (code "7") (name "/BOOT1_MIDDLE") (class "Default")
      (node (ref "U$23") (pin "2") (pinfunction "2_2") (pintype "bidirectional"))
      (node (ref "U$25") (pin "2") (pinfunction "2_2") (pintype "bidirectional"))
    )
    (net (code "8") (name "/D+") (class "Default")
      (node (ref "U$18") (pin "3") (pinfunction "D+_3") (pintype "bidirectional"))
      (node (ref "U$20") (pin "5") (pinfunction "D+_5") (pintype "bidirectional"))
    )
    (net (code "9") (name "/D-") (class "Default")
      (node (ref "U$18") (pin "2") (pinfunction "D-_2") (pintype "bidirectional"))
      (node (ref "U$20") (pin "6") (pinfunction "D-_6") (pintype "bidirectional"))
    )
    (net (code "10") (name "/GND") (class "Default")
      (node (ref "J1") (pin "19") (pinfunction "19_19") (pintype "bidirectional"))
      (node (ref "J2") (pin "1") (pinfunction "1_1") (pintype "bidirectional"))
      (node (ref "J2") (pin "2") (pinfunction "2_2") (pintype "bidirectional"))
      (node (ref "U$1") (pin "23") (pinfunction "VSS_1_23") (pintype "bidirectional"))
      (node (ref "U$1") (pin "35") (pinfunction "VSS_2_35") (pintype "bidirectional"))
      (node (ref "U$1") (pin "47") (pinfunction "VSS_3_47") (pintype "bidirectional"))
      (node (ref "U$1") (pin "8") (pinfunction "VSSA_8") (pintype "bidirectional"))
      (node (ref "U$10") (pin "2") (pinfunction "2_2") (pintype "bidirectional"))
      (node (ref "U$100") (pin "1") (pinfunction "1_1") (pintype "bidirectional"))
      (node (ref "U$101") (pin "GND") (pinfunction "GND_GND") (pintype "bidirectional"))
      (node (ref "U$102") (pin "1") (pinfunction "1_1") (pintype "bidirectional"))
      (node (ref "U$103") (pin "GND") (pinfunction "GND_GND") (pintype "bidirectional"))
      (node (ref "U$104") (pin "1") (pinfunction "1_1") (pintype "bidirectional"))
      (node (ref "U$105") (pin "GND") (pinfunction "GND_GND") (pintype "bidirectional"))
      (node (ref "U$106") (pin "1") (pinfunction "1_1") (pintype "bidirectional"))
      (node (ref "U$107") (pin "GND") (pinfunction "GND_GND") (pintype "bidirectional"))
      (node (ref "U$108") (pin "1") (pinfunction "1_1") (pintype "bidirectional"))
      (node (ref "U$109") (pin "GND") (pinfunction "GND_GND") (pintype "bidirectional"))
      (node (ref "U$11") (pin "1") (pinfunction "1_1") (pintype "bidirectional"))
      (node (ref "U$110") (pin "1") (pinfunction "1_1") (pintype "bidirectional"))
      (node (ref "U$111") (pin "GND") (pinfunction "GND_GND") (pintype "bidirectional"))
      (node (ref "U$112") (pin "1") (pinfunction "1_1") (pintype "bidirectional"))
      (node (ref "U$113") (pin "GND") (pinfunction "GND_GND") (pintype "bidirectional"))
      (node (ref "U$114") (pin "1") (pinfunction "1_1") (pintype "bidirectional"))
      (node (ref "U$115") (pin "12") (pinfunction "VSS_12") (pintype "bidirectional"))
      (node (ref "U$115") (pin "2") (pinfunction "A1_2") (pintype "bidirectional"))
      (node (ref "U$115") (pin "21") (pinfunction "A0_21") (pintype "bidirectional"))
      (node (ref "U$115") (pin "3") (pinfunction "A2_3") (pintype "bidirectional"))
      (node (ref "U$116") (pin "1") (pinfunction "1_1") (pintype "bidirectional"))
      (node (ref "U$12") (pin "2") (pinfunction "2_2") (pintype "bidirectional"))
      (node (ref "U$120") (pin "1") (pinfunction "1_1") (pintype "bidirectional"))
      (node (ref "U$126") (pin "2") (pinfunction "2_2") (pintype "bidirectional"))
      (node (ref "U$13") (pin "1") (pinfunction "1_1") (pintype "bidirectional"))
      (node (ref "U$130") (pin "1") (pinfunction "1_1") (pintype "bidirectional"))
      (node (ref "U$14") (pin "1") (pinfunction "1_1") (pintype "bidirectional"))
      (node (ref "U$15") (pin "1") (pinfunction "1_1") (pintype "bidirectional"))
      (node (ref "U$16") (pin "1") (pinfunction "1_1") (pintype "bidirectional"))
      (node (ref "U$17") (pin "1") (pinfunction "1_1") (pintype "bidirectional"))
      (node (ref "U$18") (pin "4") (pinfunction "GND_4") (pintype "bidirectional"))
      (node (ref "U$18") (pin "5") (pinfunction "GND3_5") (pintype "bidirectional"))
      (node (ref "U$18") (pin "6") (pinfunction "GND2_6") (pintype "bidirectional"))
      (node (ref "U$20") (pin "1") (pinfunction "GND_1") (pintype "bidirectional"))
      (node (ref "U$21") (pin "1") (pinfunction "1_1") (pintype "bidirectional"))
      (node (ref "U$22") (pin "3") (pinfunction "3_3") (pintype "bidirectional"))
      (node (ref "U$23") (pin "3") (pinfunction "3_3") (pintype "bidirectional"))
      (node (ref "U$26") (pin "1") (pinfunction "1_1") (pintype "bidirectional"))
      (node (ref "U$29") (pin "1") (pinfunction "A0_1") (pintype "bidirectional"))
      (node (ref "U$29") (pin "14") (pinfunction "VSS_14") (pintype "bidirectional"))
      (node (ref "U$29") (pin "2") (pinfunction "A1_2") (pintype "bidirectional"))
      (node (ref "U$29") (pin "24") (pinfunction "A5_24") (pintype "bidirectional"))
      (node (ref "U$29") (pin "25") (pinfunction "EXTCLK_25") (pintype "bidirectional"))
      (node (ref "U$29") (pin "3") (pinfunction "A2_3") (pintype "bidirectional"))
      (node (ref "U$29") (pin "5") (pinfunction "A4_5") (pintype "bidirectional"))
      (node (ref "U$3") (pin "1") (pinfunction "1_1") (pintype "bidirectional"))
      (node (ref "U$30") (pin "1") (pinfunction "A0_1") (pintype "bidirectional"))
      (node (ref "U$30") (pin "14") (pinfunction "VSS_14") (pintype "bidirectional"))
      (node (ref "U$30") (pin "2") (pinfunction "A1_2") (pintype "bidirectional"))
      (node (ref "U$30") (pin "24") (pinfunction "A5_24") (pintype "bidirectional"))
      (node (ref "U$30") (pin "25") (pinfunction "EXTCLK_25") (pintype "bidirectional"))
      (node (ref "U$30") (pin "4") (pinfunction "A3_4") (pintype "bidirectional"))
      (node (ref "U$30") (pin "5") (pinfunction "A4_5") (pintype "bidirectional"))
      (node (ref "U$31") (pin "1") (pinfunction "1_1") (pintype "bidirectional"))
      (node (ref "U$32") (pin "2") (pinfunction "2_2") (pintype "bidirectional"))
      (node (ref "U$33") (pin "2") (pinfunction "2_2") (pintype "bidirectional"))
      (node (ref "U$34") (pin "1") (pinfunction "1_1") (pintype "bidirectional"))
      (node (ref "U$35") (pin "16") (pinfunction "BIN2_16") (pintype "bidirectional"))
      (node (ref "U$35") (pin "18") (pinfunction "GND_18") (pintype "bidirectional"))
      (node (ref "U$35") (pin "22") (pinfunction "AIN2_22") (pintype "bidirectional"))
      (node (ref "U$36") (pin "16") (pinfunction "BIN2_16") (pintype "bidirectional"))
      (node (ref "U$36") (pin "18") (pinfunction "GND_18") (pintype "bidirectional"))
      (node (ref "U$36") (pin "22") (pinfunction "AIN2_22") (pintype "bidirectional"))
      (node (ref "U$39") (pin "1") (pinfunction "1_1") (pintype "bidirectional"))
      (node (ref "U$4") (pin "1") (pinfunction "1_1") (pintype "bidirectional"))
      (node (ref "U$42") (pin "1") (pinfunction "1_1") (pintype "bidirectional"))
      (node (ref "U$43") (pin "16") (pinfunction "BIN2_16") (pintype "bidirectional"))
      (node (ref "U$43") (pin "18") (pinfunction "GND_18") (pintype "bidirectional"))
      (node (ref "U$43") (pin "22") (pinfunction "AIN2_22") (pintype "bidirectional"))
      (node (ref "U$46") (pin "1") (pinfunction "1_1") (pintype "bidirectional"))
      (node (ref "U$47") (pin "16") (pinfunction "BIN2_16") (pintype "bidirectional"))
      (node (ref "U$47") (pin "18") (pinfunction "GND_18") (pintype "bidirectional"))
      (node (ref "U$47") (pin "22") (pinfunction "AIN2_22") (pintype "bidirectional"))
      (node (ref "U$50") (pin "1") (pinfunction "1_1") (pintype "bidirectional"))
      (node (ref "U$51") (pin "16") (pinfunction "BIN2_16") (pintype "bidirectional"))
      (node (ref "U$51") (pin "18") (pinfunction "GND_18") (pintype "bidirectional"))
      (node (ref "U$51") (pin "22") (pinfunction "AIN2_22") (pintype "bidirectional"))
      (node (ref "U$54") (pin "1") (pinfunction "1_1") (pintype "bidirectional"))
      (node (ref "U$55") (pin "16") (pinfunction "BIN2_16") (pintype "bidirectional"))
      (node (ref "U$55") (pin "18") (pinfunction "GND_18") (pintype "bidirectional"))
      (node (ref "U$55") (pin "22") (pinfunction "AIN2_22") (pintype "bidirectional"))
      (node (ref "U$58") (pin "1") (pinfunction "1_1") (pintype "bidirectional"))
      (node (ref "U$59") (pin "16") (pinfunction "BIN2_16") (pintype "bidirectional"))
      (node (ref "U$59") (pin "18") (pinfunction "GND_18") (pintype "bidirectional"))
      (node (ref "U$59") (pin "22") (pinfunction "AIN2_22") (pintype "bidirectional"))
      (node (ref "U$6") (pin "2") (pinfunction "GND_2") (pintype "bidirectional"))
      (node (ref "U$6") (pin "3") (pinfunction "GND2_3") (pintype "bidirectional"))
      (node (ref "U$62") (pin "1") (pinfunction "1_1") (pintype "bidirectional"))
      (node (ref "U$63") (pin "16") (pinfunction "BIN2_16") (pintype "bidirectional"))
      (node (ref "U$63") (pin "18") (pinfunction "GND_18") (pintype "bidirectional"))
      (node (ref "U$63") (pin "22") (pinfunction "AIN2_22") (pintype "bidirectional"))
      (node (ref "U$66") (pin "1") (pinfunction "1_1") (pintype "bidirectional"))
      (node (ref "U$67") (pin "16") (pinfunction "BIN2_16") (pintype "bidirectional"))
      (node (ref "U$67") (pin "18") (pinfunction "GND_18") (pintype "bidirectional"))
      (node (ref "U$67") (pin "22") (pinfunction "AIN2_22") (pintype "bidirectional"))
      (node (ref "U$7") (pin "1") (pinfunction "1_1") (pintype "bidirectional"))
      (node (ref "U$70") (pin "1") (pinfunction "1_1") (pintype "bidirectional"))
      (node (ref "U$71") (pin "16") (pinfunction "BIN2_16") (pintype "bidirectional"))
      (node (ref "U$71") (pin "18") (pinfunction "GND_18") (pintype "bidirectional"))
      (node (ref "U$71") (pin "22") (pinfunction "AIN2_22") (pintype "bidirectional"))
      (node (ref "U$74") (pin "1") (pinfunction "1_1") (pintype "bidirectional"))
      (node (ref "U$75") (pin "16") (pinfunction "BIN2_16") (pintype "bidirectional"))
      (node (ref "U$75") (pin "18") (pinfunction "GND_18") (pintype "bidirectional"))
      (node (ref "U$75") (pin "22") (pinfunction "AIN2_22") (pintype "bidirectional"))
      (node (ref "U$78") (pin "1") (pinfunction "1_1") (pintype "bidirectional"))
      (node (ref "U$79") (pin "16") (pinfunction "BIN2_16") (pintype "bidirectional"))
      (node (ref "U$79") (pin "18") (pinfunction "GND_18") (pintype "bidirectional"))
      (node (ref "U$79") (pin "22") (pinfunction "AIN2_22") (pintype "bidirectional"))
      (node (ref "U$8") (pin "1") (pinfunction "1_1") (pintype "bidirectional"))
      (node (ref "U$82") (pin "1") (pinfunction "1_1") (pintype "bidirectional"))
      (node (ref "U$83") (pin "16") (pinfunction "BIN2_16") (pintype "bidirectional"))
      (node (ref "U$83") (pin "18") (pinfunction "GND_18") (pintype "bidirectional"))
      (node (ref "U$83") (pin "22") (pinfunction "AIN2_22") (pintype "bidirectional"))
      (node (ref "U$86") (pin "1") (pinfunction "1_1") (pintype "bidirectional"))
      (node (ref "U$87") (pin "16") (pinfunction "BIN2_16") (pintype "bidirectional"))
      (node (ref "U$87") (pin "18") (pinfunction "GND_18") (pintype "bidirectional"))
      (node (ref "U$87") (pin "22") (pinfunction "AIN2_22") (pintype "bidirectional"))
      (node (ref "U$9") (pin "1") (pinfunction "GND_1") (pintype "bidirectional"))
      (node (ref "U$90") (pin "1") (pinfunction "1_1") (pintype "bidirectional"))
      (node (ref "U$91") (pin "16") (pinfunction "BIN2_16") (pintype "bidirectional"))
      (node (ref "U$91") (pin "18") (pinfunction "GND_18") (pintype "bidirectional"))
      (node (ref "U$91") (pin "22") (pinfunction "AIN2_22") (pintype "bidirectional"))
      (node (ref "U$94") (pin "1") (pinfunction "1_1") (pintype "bidirectional"))
      (node (ref "U$95") (pin "GND") (pinfunction "GND_GND") (pintype "bidirectional"))
      (node (ref "U$96") (pin "GND") (pinfunction "GND_GND") (pintype "bidirectional"))
      (node (ref "U$97") (pin "1") (pinfunction "1_1") (pintype "bidirectional"))
      (node (ref "U$98") (pin "1") (pinfunction "1_1") (pintype "bidirectional"))
      (node (ref "U$99") (pin "GND") (pinfunction "GND_GND") (pintype "bidirectional"))
    )
    (net (code "11") (name "/I2C1_SCL") (class "Default")
      (node (ref "J1") (pin "14") (pinfunction "14_14") (pintype "bidirectional"))
      (node (ref "U$1") (pin "42") (pinfunction "PB6_42") (pintype "bidirectional"))
      (node (ref "U$115") (pin "22") (pinfunction "SCL_22") (pintype "bidirectional"))
      (node (ref "U$129") (pin "1") (pinfunction "1_1") (pintype "bidirectional"))
      (node (ref "U$29") (pin "26") (pinfunction "SCL_26") (pintype "bidirectional"))
      (node (ref "U$30") (pin "26") (pinfunction "SCL_26") (pintype "bidirectional"))
    )
    (net (code "12") (name "/I2C1_SDA") (class "Default")
      (node (ref "J1") (pin "15") (pinfunction "15_15") (pintype "bidirectional"))
      (node (ref "U$1") (pin "43") (pinfunction "PB7_43") (pintype "bidirectional"))
      (node (ref "U$115") (pin "23") (pinfunction "SDA_23") (pintype "bidirectional"))
      (node (ref "U$128") (pin "1") (pinfunction "1_1") (pintype "bidirectional"))
      (node (ref "U$29") (pin "27") (pinfunction "SDA_27") (pintype "bidirectional"))
      (node (ref "U$30") (pin "27") (pinfunction "SDA_27") (pintype "bidirectional"))
    )
    (net (code "13") (name "/OE#1") (class "Default")
      (node (ref "U$29") (pin "23") (pinfunction "OE#_23") (pintype "bidirectional"))
      (node (ref "U$31") (pin "2") (pinfunction "2_2") (pintype "bidirectional"))
    )
    (net (code "14") (name "/OE#2") (class "Default")
      (node (ref "U$30") (pin "23") (pinfunction "OE#_23") (pintype "bidirectional"))
      (node (ref "U$34") (pin "2") (pinfunction "2_2") (pintype "bidirectional"))
    )
    (net (code "15") (name "/OSC_IN") (class "Default")
      (node (ref "U$1") (pin "5") (pinfunction "PD0-OSC_IN_5") (pintype "bidirectional"))
      (node (ref "U$2") (pin "1") (pinfunction "1_1") (pintype "bidirectional"))
      (node (ref "U$3") (pin "2") (pinfunction "2_2") (pintype "bidirectional"))
      (node (ref "U$5") (pin "1") (pinfunction "1_1") (pintype "bidirectional"))
    )
    (net (code "16") (name "/OSC_OUT") (class "Default")
      (node (ref "U$1") (pin "6") (pinfunction "PD1-OSC_OUT_6") (pintype "bidirectional"))
      (node (ref "U$2") (pin "2") (pinfunction "2_2") (pintype "bidirectional"))
      (node (ref "U$4") (pin "2") (pinfunction "2_2") (pintype "bidirectional"))
      (node (ref "U$5") (pin "2") (pinfunction "2_2") (pintype "bidirectional"))
    )
    (net (code "17") (name "/PA0") (class "Default")
      (node (ref "J2") (pin "16") (pinfunction "16_16") (pintype "bidirectional"))
      (node (ref "U$1") (pin "10") (pinfunction "PA0-WKUP_10") (pintype "bidirectional"))
    )
    (net (code "18") (name "/PA1") (class "Default")
      (node (ref "J2") (pin "15") (pinfunction "15_15") (pintype "bidirectional"))
      (node (ref "U$1") (pin "11") (pinfunction "PA1_11") (pintype "bidirectional"))
    )
    (net (code "19") (name "/PA2") (class "Default")
      (node (ref "J2") (pin "14") (pinfunction "14_14") (pintype "bidirectional"))
      (node (ref "U$1") (pin "12") (pinfunction "PA2_12") (pintype "bidirectional"))
    )
    (net (code "20") (name "/PA3") (class "Default")
      (node (ref "J2") (pin "13") (pinfunction "13_13") (pintype "bidirectional"))
      (node (ref "U$1") (pin "13") (pinfunction "PA3_13") (pintype "bidirectional"))
    )
    (net (code "21") (name "/PA4") (class "Default")
      (node (ref "J2") (pin "12") (pinfunction "12_12") (pintype "bidirectional"))
      (node (ref "U$1") (pin "14") (pinfunction "PA4_14") (pintype "bidirectional"))
    )
    (net (code "22") (name "/PA7") (class "Default")
      (node (ref "J2") (pin "9") (pinfunction "9_9") (pintype "bidirectional"))
      (node (ref "U$1") (pin "17") (pinfunction "PA7_17") (pintype "bidirectional"))
    )
    (net (code "23") (name "/PA8") (class "Default")
      (node (ref "J1") (pin "5") (pinfunction "5_5") (pintype "bidirectional"))
      (node (ref "U$1") (pin "29") (pinfunction "PA8_29") (pintype "bidirectional"))
    )
    (net (code "24") (name "/PA11") (class "Default")
      (node (ref "J1") (pin "8") (pinfunction "8_8") (pintype "bidirectional"))
      (node (ref "U$1") (pin "32") (pinfunction "PA11_32") (pintype "bidirectional"))
    )
    (net (code "25") (name "/PA12") (class "Default")
      (node (ref "J1") (pin "9") (pinfunction "9_9") (pintype "bidirectional"))
      (node (ref "U$1") (pin "33") (pinfunction "PA12_33") (pintype "bidirectional"))
    )
    (net (code "26") (name "/PA15") (class "Default")
      (node (ref "J1") (pin "10") (pinfunction "10_10") (pintype "bidirectional"))
      (node (ref "U$1") (pin "38") (pinfunction "PA15_38") (pintype "bidirectional"))
    )
    (net (code "27") (name "/PB0") (class "Default")
      (node (ref "J2") (pin "8") (pinfunction "8_8") (pintype "bidirectional"))
      (node (ref "U$1") (pin "18") (pinfunction "PB0_18") (pintype "bidirectional"))
    )
    (net (code "28") (name "/PB1") (class "Default")
      (node (ref "J2") (pin "7") (pinfunction "7_7") (pintype "bidirectional"))
      (node (ref "U$1") (pin "19") (pinfunction "PB1_19") (pintype "bidirectional"))
    )
    (net (code "29") (name "/PB3") (class "Default")
      (node (ref "J1") (pin "11") (pinfunction "11_11") (pintype "bidirectional"))
      (node (ref "U$1") (pin "39") (pinfunction "PB3_39") (pintype "bidirectional"))
    )
    (net (code "30") (name "/PB4") (class "Default")
      (node (ref "J1") (pin "12") (pinfunction "12_12") (pintype "bidirectional"))
      (node (ref "U$1") (pin "40") (pinfunction "PB4_40") (pintype "bidirectional"))
    )
    (net (code "31") (name "/PB5") (class "Default")
      (node (ref "J1") (pin "13") (pinfunction "13_13") (pintype "bidirectional"))
      (node (ref "U$1") (pin "41") (pinfunction "PB5_41") (pintype "bidirectional"))
    )
    (net (code "32") (name "/PB8") (class "Default")
      (node (ref "J1") (pin "16") (pinfunction "16_16") (pintype "bidirectional"))
      (node (ref "U$1") (pin "45") (pinfunction "PB8_45") (pintype "bidirectional"))
    )
    (net (code "33") (name "/PB9") (class "Default")
      (node (ref "J1") (pin "17") (pinfunction "17_17") (pintype "bidirectional"))
      (node (ref "U$1") (pin "46") (pinfunction "PB9_46") (pintype "bidirectional"))
    )
    (net (code "34") (name "/PB10") (class "Default")
      (node (ref "J2") (pin "6") (pinfunction "6_6") (pintype "bidirectional"))
      (node (ref "U$1") (pin "21") (pinfunction "PB10_21") (pintype "bidirectional"))
    )
    (net (code "35") (name "/PB11") (class "Default")
      (node (ref "J2") (pin "5") (pinfunction "5_5") (pintype "bidirectional"))
      (node (ref "U$1") (pin "22") (pinfunction "PB11_22") (pintype "bidirectional"))
    )
    (net (code "36") (name "/PB12") (class "Default")
      (node (ref "J1") (pin "1") (pinfunction "1_1") (pintype "bidirectional"))
      (node (ref "U$1") (pin "25") (pinfunction "PB12_25") (pintype "bidirectional"))
    )
    (net (code "37") (name "/PB13") (class "Default")
      (node (ref "J1") (pin "2") (pinfunction "2_2") (pintype "bidirectional"))
      (node (ref "U$1") (pin "26") (pinfunction "PB13_26") (pintype "bidirectional"))
    )
    (net (code "38") (name "/PB14") (class "Default")
      (node (ref "J1") (pin "3") (pinfunction "3_3") (pintype "bidirectional"))
      (node (ref "U$1") (pin "27") (pinfunction "PB14_27") (pintype "bidirectional"))
    )
    (net (code "39") (name "/PB15") (class "Default")
      (node (ref "J1") (pin "4") (pinfunction "4_4") (pintype "bidirectional"))
      (node (ref "U$1") (pin "28") (pinfunction "PB15_28") (pintype "bidirectional"))
    )
    (net (code "40") (name "/PC13") (class "Default")
      (node (ref "J2") (pin "19") (pinfunction "19_19") (pintype "bidirectional"))
      (node (ref "U$1") (pin "2") (pinfunction "PC13-TAMPER-RTC_2") (pintype "bidirectional"))
      (node (ref "U$127") (pin "2") (pinfunction "2_2") (pintype "bidirectional"))
    )
    (net (code "41") (name "/PC14") (class "Default")
      (node (ref "J2") (pin "18") (pinfunction "18_18") (pintype "bidirectional"))
      (node (ref "U$1") (pin "3") (pinfunction "PC14-OSC32_IN_3") (pintype "bidirectional"))
      (node (ref "U$6") (pin "1") (pinfunction "OSC1_1") (pintype "bidirectional"))
      (node (ref "U$8") (pin "2") (pinfunction "2_2") (pintype "bidirectional"))
    )
    (net (code "42") (name "/PC15") (class "Default")
      (node (ref "J2") (pin "17") (pinfunction "17_17") (pintype "bidirectional"))
      (node (ref "U$1") (pin "4") (pinfunction "PC15-OSC32_OUT_4") (pintype "bidirectional"))
      (node (ref "U$6") (pin "4") (pinfunction "OSC2_4") (pintype "bidirectional"))
      (node (ref "U$7") (pin "2") (pinfunction "2_2") (pintype "bidirectional"))
    )
    (net (code "43") (name "/PGND1") (class "Default")
      (node (ref "U$117") (pin "1") (pinfunction "1_1") (pintype "bidirectional"))
      (node (ref "U$119") (pin "2") (pinfunction "2_2") (pintype "bidirectional"))
      (node (ref "U$120") (pin "2") (pinfunction "2_2") (pintype "bidirectional"))
      (node (ref "U$35") (pin "10") (pinfunction "PGND2-2_10") (pintype "bidirectional"))
      (node (ref "U$35") (pin "3") (pinfunction "PGND1_3") (pintype "bidirectional"))
      (node (ref "U$35") (pin "4") (pinfunction "PGND1-2_4") (pintype "bidirectional"))
      (node (ref "U$35") (pin "9") (pinfunction "PGND2_9") (pintype "bidirectional"))
      (node (ref "U$37") (pin "1") (pinfunction "1_1") (pintype "bidirectional"))
      (node (ref "U$38") (pin "2") (pinfunction "2_2") (pintype "bidirectional"))
      (node (ref "U$43") (pin "10") (pinfunction "PGND2-2_10") (pintype "bidirectional"))
      (node (ref "U$43") (pin "3") (pinfunction "PGND1_3") (pintype "bidirectional"))
      (node (ref "U$43") (pin "4") (pinfunction "PGND1-2_4") (pintype "bidirectional"))
      (node (ref "U$43") (pin "9") (pinfunction "PGND2_9") (pintype "bidirectional"))
      (node (ref "U$44") (pin "1") (pinfunction "1_1") (pintype "bidirectional"))
      (node (ref "U$45") (pin "2") (pinfunction "2_2") (pintype "bidirectional"))
      (node (ref "U$51") (pin "10") (pinfunction "PGND2-2_10") (pintype "bidirectional"))
      (node (ref "U$51") (pin "3") (pinfunction "PGND1_3") (pintype "bidirectional"))
      (node (ref "U$51") (pin "4") (pinfunction "PGND1-2_4") (pintype "bidirectional"))
      (node (ref "U$51") (pin "9") (pinfunction "PGND2_9") (pintype "bidirectional"))
      (node (ref "U$52") (pin "1") (pinfunction "1_1") (pintype "bidirectional"))
      (node (ref "U$53") (pin "2") (pinfunction "2_2") (pintype "bidirectional"))
      (node (ref "U$55") (pin "10") (pinfunction "PGND2-2_10") (pintype "bidirectional"))
      (node (ref "U$55") (pin "3") (pinfunction "PGND1_3") (pintype "bidirectional"))
      (node (ref "U$55") (pin "4") (pinfunction "PGND1-2_4") (pintype "bidirectional"))
      (node (ref "U$55") (pin "9") (pinfunction "PGND2_9") (pintype "bidirectional"))
      (node (ref "U$56") (pin "1") (pinfunction "1_1") (pintype "bidirectional"))
      (node (ref "U$57") (pin "2") (pinfunction "2_2") (pintype "bidirectional"))
      (node (ref "U$63") (pin "10") (pinfunction "PGND2-2_10") (pintype "bidirectional"))
      (node (ref "U$63") (pin "3") (pinfunction "PGND1_3") (pintype "bidirectional"))
      (node (ref "U$63") (pin "4") (pinfunction "PGND1-2_4") (pintype "bidirectional"))
      (node (ref "U$63") (pin "9") (pinfunction "PGND2_9") (pintype "bidirectional"))
      (node (ref "U$64") (pin "1") (pinfunction "1_1") (pintype "bidirectional"))
      (node (ref "U$65") (pin "2") (pinfunction "2_2") (pintype "bidirectional"))
      (node (ref "U$71") (pin "10") (pinfunction "PGND2-2_10") (pintype "bidirectional"))
      (node (ref "U$71") (pin "3") (pinfunction "PGND1_3") (pintype "bidirectional"))
      (node (ref "U$71") (pin "4") (pinfunction "PGND1-2_4") (pintype "bidirectional"))
      (node (ref "U$71") (pin "9") (pinfunction "PGND2_9") (pintype "bidirectional"))
      (node (ref "U$72") (pin "1") (pinfunction "1_1") (pintype "bidirectional"))
      (node (ref "U$73") (pin "2") (pinfunction "2_2") (pintype "bidirectional"))
      (node (ref "U$75") (pin "10") (pinfunction "PGND2-2_10") (pintype "bidirectional"))
      (node (ref "U$75") (pin "3") (pinfunction "PGND1_3") (pintype "bidirectional"))
      (node (ref "U$75") (pin "4") (pinfunction "PGND1-2_4") (pintype "bidirectional"))
      (node (ref "U$75") (pin "9") (pinfunction "PGND2_9") (pintype "bidirectional"))
      (node (ref "U$76") (pin "1") (pinfunction "1_1") (pintype "bidirectional"))
      (node (ref "U$77") (pin "2") (pinfunction "2_2") (pintype "bidirectional"))
      (node (ref "U$83") (pin "10") (pinfunction "PGND2-2_10") (pintype "bidirectional"))
      (node (ref "U$83") (pin "3") (pinfunction "PGND1_3") (pintype "bidirectional"))
      (node (ref "U$83") (pin "4") (pinfunction "PGND1-2_4") (pintype "bidirectional"))
      (node (ref "U$83") (pin "9") (pinfunction "PGND2_9") (pintype "bidirectional"))
      (node (ref "U$84") (pin "1") (pinfunction "1_1") (pintype "bidirectional"))
      (node (ref "U$85") (pin "2") (pinfunction "2_2") (pintype "bidirectional"))
    )
    (net (code "44") (name "/PGND2") (class "Default")
      (node (ref "U$118") (pin "1") (pinfunction "1_1") (pintype "bidirectional"))
      (node (ref "U$119") (pin "1") (pinfunction "1_1") (pintype "bidirectional"))
      (node (ref "U$36") (pin "10") (pinfunction "PGND2-2_10") (pintype "bidirectional"))
      (node (ref "U$36") (pin "3") (pinfunction "PGND1_3") (pintype "bidirectional"))
      (node (ref "U$36") (pin "4") (pinfunction "PGND1-2_4") (pintype "bidirectional"))
      (node (ref "U$36") (pin "9") (pinfunction "PGND2_9") (pintype "bidirectional"))
      (node (ref "U$40") (pin "1") (pinfunction "1_1") (pintype "bidirectional"))
      (node (ref "U$41") (pin "2") (pinfunction "2_2") (pintype "bidirectional"))
      (node (ref "U$47") (pin "10") (pinfunction "PGND2-2_10") (pintype "bidirectional"))
      (node (ref "U$47") (pin "3") (pinfunction "PGND1_3") (pintype "bidirectional"))
      (node (ref "U$47") (pin "4") (pinfunction "PGND1-2_4") (pintype "bidirectional"))
      (node (ref "U$47") (pin "9") (pinfunction "PGND2_9") (pintype "bidirectional"))
      (node (ref "U$48") (pin "1") (pinfunction "1_1") (pintype "bidirectional"))
      (node (ref "U$49") (pin "2") (pinfunction "2_2") (pintype "bidirectional"))
      (node (ref "U$59") (pin "10") (pinfunction "PGND2-2_10") (pintype "bidirectional"))
      (node (ref "U$59") (pin "3") (pinfunction "PGND1_3") (pintype "bidirectional"))
      (node (ref "U$59") (pin "4") (pinfunction "PGND1-2_4") (pintype "bidirectional"))
      (node (ref "U$59") (pin "9") (pinfunction "PGND2_9") (pintype "bidirectional"))
      (node (ref "U$60") (pin "1") (pinfunction "1_1") (pintype "bidirectional"))
      (node (ref "U$61") (pin "2") (pinfunction "2_2") (pintype "bidirectional"))
      (node (ref "U$67") (pin "10") (pinfunction "PGND2-2_10") (pintype "bidirectional"))
      (node (ref "U$67") (pin "3") (pinfunction "PGND1_3") (pintype "bidirectional"))
      (node (ref "U$67") (pin "4") (pinfunction "PGND1-2_4") (pintype "bidirectional"))
      (node (ref "U$67") (pin "9") (pinfunction "PGND2_9") (pintype "bidirectional"))
      (node (ref "U$68") (pin "1") (pinfunction "1_1") (pintype "bidirectional"))
      (node (ref "U$69") (pin "2") (pinfunction "2_2") (pintype "bidirectional"))
      (node (ref "U$79") (pin "10") (pinfunction "PGND2-2_10") (pintype "bidirectional"))
      (node (ref "U$79") (pin "3") (pinfunction "PGND1_3") (pintype "bidirectional"))
      (node (ref "U$79") (pin "4") (pinfunction "PGND1-2_4") (pintype "bidirectional"))
      (node (ref "U$79") (pin "9") (pinfunction "PGND2_9") (pintype "bidirectional"))
      (node (ref "U$80") (pin "1") (pinfunction "1_1") (pintype "bidirectional"))
      (node (ref "U$81") (pin "2") (pinfunction "2_2") (pintype "bidirectional"))
      (node (ref "U$87") (pin "10") (pinfunction "PGND2-2_10") (pintype "bidirectional"))
      (node (ref "U$87") (pin "3") (pinfunction "PGND1_3") (pintype "bidirectional"))
      (node (ref "U$87") (pin "4") (pinfunction "PGND1-2_4") (pintype "bidirectional"))
      (node (ref "U$87") (pin "9") (pinfunction "PGND2_9") (pintype "bidirectional"))
      (node (ref "U$88") (pin "1") (pinfunction "1_1") (pintype "bidirectional"))
      (node (ref "U$89") (pin "2") (pinfunction "2_2") (pintype "bidirectional"))
      (node (ref "U$91") (pin "10") (pinfunction "PGND2-2_10") (pintype "bidirectional"))
      (node (ref "U$91") (pin "3") (pinfunction "PGND1_3") (pintype "bidirectional"))
      (node (ref "U$91") (pin "4") (pinfunction "PGND1-2_4") (pintype "bidirectional"))
      (node (ref "U$91") (pin "9") (pinfunction "PGND2_9") (pintype "bidirectional"))
      (node (ref "U$92") (pin "1") (pinfunction "1_1") (pintype "bidirectional"))
      (node (ref "U$93") (pin "2") (pinfunction "2_2") (pintype "bidirectional"))
    )
    (net (code "45") (name "/PUMP0_H") (class "Default")
      (node (ref "U$121") (pin "1") (pinfunction "P1_1") (pintype "bidirectional"))
      (node (ref "U$35") (pin "1") (pinfunction "AO1_1") (pintype "bidirectional"))
      (node (ref "U$35") (pin "2") (pinfunction "AO1-2_2") (pintype "bidirectional"))
    )
    (net (code "46") (name "/PUMP0_L") (class "Default")
      (node (ref "U$121") (pin "2") (pinfunction "P2_2") (pintype "bidirectional"))
      (node (ref "U$35") (pin "5") (pinfunction "A02_5") (pintype "bidirectional"))
      (node (ref "U$35") (pin "6") (pinfunction "A02-2_6") (pintype "bidirectional"))
    )
    (net (code "47") (name "/PUMP1_H") (class "Default")
      (node (ref "U$121") (pin "3") (pinfunction "P3_3") (pintype "bidirectional"))
      (node (ref "U$35") (pin "11") (pinfunction "BO1_11") (pintype "bidirectional"))
      (node (ref "U$35") (pin "12") (pinfunction "BO1-2_12") (pintype "bidirectional"))
    )
    (net (code "48") (name "/PUMP1_L") (class "Default")
      (node (ref "U$121") (pin "4") (pinfunction "P4_4") (pintype "bidirectional"))
      (node (ref "U$35") (pin "7") (pinfunction "BO2_7") (pintype "bidirectional"))
      (node (ref "U$35") (pin "8") (pinfunction "BO2-2_8") (pintype "bidirectional"))
    )
    (net (code "49") (name "/PUMP2_H") (class "Default")
      (node (ref "U$121") (pin "5") (pinfunction "P5_5") (pintype "bidirectional"))
      (node (ref "U$36") (pin "1") (pinfunction "AO1_1") (pintype "bidirectional"))
      (node (ref "U$36") (pin "2") (pinfunction "AO1-2_2") (pintype "bidirectional"))
    )
    (net (code "50") (name "/PUMP2_L") (class "Default")
      (node (ref "U$121") (pin "6") (pinfunction "P6_6") (pintype "bidirectional"))
      (node (ref "U$36") (pin "5") (pinfunction "A02_5") (pintype "bidirectional"))
      (node (ref "U$36") (pin "6") (pinfunction "A02-2_6") (pintype "bidirectional"))
    )
    (net (code "51") (name "/PUMP3_H") (class "Default")
      (node (ref "U$121") (pin "7") (pinfunction "P7_7") (pintype "bidirectional"))
      (node (ref "U$36") (pin "11") (pinfunction "BO1_11") (pintype "bidirectional"))
      (node (ref "U$36") (pin "12") (pinfunction "BO1-2_12") (pintype "bidirectional"))
    )
    (net (code "52") (name "/PUMP3_L") (class "Default")
      (node (ref "U$121") (pin "8") (pinfunction "P8_8") (pintype "bidirectional"))
      (node (ref "U$36") (pin "7") (pinfunction "BO2_7") (pintype "bidirectional"))
      (node (ref "U$36") (pin "8") (pinfunction "BO2-2_8") (pintype "bidirectional"))
    )
    (net (code "53") (name "/PUMP4_H") (class "Default")
      (node (ref "U$121") (pin "9") (pinfunction "P9_9") (pintype "bidirectional"))
      (node (ref "U$43") (pin "1") (pinfunction "AO1_1") (pintype "bidirectional"))
      (node (ref "U$43") (pin "2") (pinfunction "AO1-2_2") (pintype "bidirectional"))
    )
    (net (code "54") (name "/PUMP4_L") (class "Default")
      (node (ref "U$121") (pin "10") (pinfunction "P10_10") (pintype "bidirectional"))
      (node (ref "U$43") (pin "5") (pinfunction "A02_5") (pintype "bidirectional"))
      (node (ref "U$43") (pin "6") (pinfunction "A02-2_6") (pintype "bidirectional"))
    )
    (net (code "55") (name "/PUMP5_H") (class "Default")
      (node (ref "U$121") (pin "11") (pinfunction "P11_11") (pintype "bidirectional"))
      (node (ref "U$43") (pin "11") (pinfunction "BO1_11") (pintype "bidirectional"))
      (node (ref "U$43") (pin "12") (pinfunction "BO1-2_12") (pintype "bidirectional"))
    )
    (net (code "56") (name "/PUMP5_L") (class "Default")
      (node (ref "U$121") (pin "12") (pinfunction "P12_12") (pintype "bidirectional"))
      (node (ref "U$43") (pin "7") (pinfunction "BO2_7") (pintype "bidirectional"))
      (node (ref "U$43") (pin "8") (pinfunction "BO2-2_8") (pintype "bidirectional"))
    )
    (net (code "57") (name "/PUMP6_H") (class "Default")
      (node (ref "U$121") (pin "13") (pinfunction "P13_13") (pintype "bidirectional"))
      (node (ref "U$47") (pin "1") (pinfunction "AO1_1") (pintype "bidirectional"))
      (node (ref "U$47") (pin "2") (pinfunction "AO1-2_2") (pintype "bidirectional"))
    )
    (net (code "58") (name "/PUMP6_L") (class "Default")
      (node (ref "U$121") (pin "14") (pinfunction "P14_14") (pintype "bidirectional"))
      (node (ref "U$47") (pin "5") (pinfunction "A02_5") (pintype "bidirectional"))
      (node (ref "U$47") (pin "6") (pinfunction "A02-2_6") (pintype "bidirectional"))
    )
    (net (code "59") (name "/PUMP7_H") (class "Default")
      (node (ref "U$121") (pin "15") (pinfunction "P15_15") (pintype "bidirectional"))
      (node (ref "U$47") (pin "11") (pinfunction "BO1_11") (pintype "bidirectional"))
      (node (ref "U$47") (pin "12") (pinfunction "BO1-2_12") (pintype "bidirectional"))
    )
    (net (code "60") (name "/PUMP7_L") (class "Default")
      (node (ref "U$121") (pin "16") (pinfunction "P16_16") (pintype "bidirectional"))
      (node (ref "U$47") (pin "7") (pinfunction "BO2_7") (pintype "bidirectional"))
      (node (ref "U$47") (pin "8") (pinfunction "BO2-2_8") (pintype "bidirectional"))
    )
    (net (code "61") (name "/PUMP8_H") (class "Default")
      (node (ref "U$121") (pin "17") (pinfunction "P17_17") (pintype "bidirectional"))
      (node (ref "U$51") (pin "1") (pinfunction "AO1_1") (pintype "bidirectional"))
      (node (ref "U$51") (pin "2") (pinfunction "AO1-2_2") (pintype "bidirectional"))
    )
    (net (code "62") (name "/PUMP8_L") (class "Default")
      (node (ref "U$121") (pin "18") (pinfunction "P18_18") (pintype "bidirectional"))
      (node (ref "U$51") (pin "5") (pinfunction "A02_5") (pintype "bidirectional"))
      (node (ref "U$51") (pin "6") (pinfunction "A02-2_6") (pintype "bidirectional"))
    )
    (net (code "63") (name "/PUMP9_H") (class "Default")
      (node (ref "U$121") (pin "19") (pinfunction "P19_19") (pintype "bidirectional"))
      (node (ref "U$51") (pin "11") (pinfunction "BO1_11") (pintype "bidirectional"))
      (node (ref "U$51") (pin "12") (pinfunction "BO1-2_12") (pintype "bidirectional"))
    )
    (net (code "64") (name "/PUMP9_L") (class "Default")
      (node (ref "U$121") (pin "20") (pinfunction "P20_20") (pintype "bidirectional"))
      (node (ref "U$51") (pin "7") (pinfunction "BO2_7") (pintype "bidirectional"))
      (node (ref "U$51") (pin "8") (pinfunction "BO2-2_8") (pintype "bidirectional"))
    )
    (net (code "65") (name "/PUMP10_H") (class "Default")
      (node (ref "U$122") (pin "1") (pinfunction "P1_1") (pintype "bidirectional"))
      (node (ref "U$55") (pin "1") (pinfunction "AO1_1") (pintype "bidirectional"))
      (node (ref "U$55") (pin "2") (pinfunction "AO1-2_2") (pintype "bidirectional"))
    )
    (net (code "66") (name "/PUMP10_L") (class "Default")
      (node (ref "U$122") (pin "2") (pinfunction "P2_2") (pintype "bidirectional"))
      (node (ref "U$55") (pin "5") (pinfunction "A02_5") (pintype "bidirectional"))
      (node (ref "U$55") (pin "6") (pinfunction "A02-2_6") (pintype "bidirectional"))
    )
    (net (code "67") (name "/PUMP11_H") (class "Default")
      (node (ref "U$122") (pin "3") (pinfunction "P3_3") (pintype "bidirectional"))
      (node (ref "U$55") (pin "11") (pinfunction "BO1_11") (pintype "bidirectional"))
      (node (ref "U$55") (pin "12") (pinfunction "BO1-2_12") (pintype "bidirectional"))
    )
    (net (code "68") (name "/PUMP11_L") (class "Default")
      (node (ref "U$122") (pin "4") (pinfunction "P4_4") (pintype "bidirectional"))
      (node (ref "U$55") (pin "7") (pinfunction "BO2_7") (pintype "bidirectional"))
      (node (ref "U$55") (pin "8") (pinfunction "BO2-2_8") (pintype "bidirectional"))
    )
    (net (code "69") (name "/PUMP12_H") (class "Default")
      (node (ref "U$122") (pin "5") (pinfunction "P5_5") (pintype "bidirectional"))
      (node (ref "U$59") (pin "1") (pinfunction "AO1_1") (pintype "bidirectional"))
      (node (ref "U$59") (pin "2") (pinfunction "AO1-2_2") (pintype "bidirectional"))
    )
    (net (code "70") (name "/PUMP12_L") (class "Default")
      (node (ref "U$122") (pin "6") (pinfunction "P6_6") (pintype "bidirectional"))
      (node (ref "U$59") (pin "5") (pinfunction "A02_5") (pintype "bidirectional"))
      (node (ref "U$59") (pin "6") (pinfunction "A02-2_6") (pintype "bidirectional"))
    )
    (net (code "71") (name "/PUMP13_H") (class "Default")
      (node (ref "U$122") (pin "7") (pinfunction "P7_7") (pintype "bidirectional"))
      (node (ref "U$59") (pin "11") (pinfunction "BO1_11") (pintype "bidirectional"))
      (node (ref "U$59") (pin "12") (pinfunction "BO1-2_12") (pintype "bidirectional"))
    )
    (net (code "72") (name "/PUMP13_L") (class "Default")
      (node (ref "U$122") (pin "8") (pinfunction "P8_8") (pintype "bidirectional"))
      (node (ref "U$59") (pin "7") (pinfunction "BO2_7") (pintype "bidirectional"))
      (node (ref "U$59") (pin "8") (pinfunction "BO2-2_8") (pintype "bidirectional"))
    )
    (net (code "73") (name "/PUMP14_H") (class "Default")
      (node (ref "U$122") (pin "9") (pinfunction "P9_9") (pintype "bidirectional"))
      (node (ref "U$63") (pin "1") (pinfunction "AO1_1") (pintype "bidirectional"))
      (node (ref "U$63") (pin "2") (pinfunction "AO1-2_2") (pintype "bidirectional"))
    )
    (net (code "74") (name "/PUMP14_L") (class "Default")
      (node (ref "U$122") (pin "10") (pinfunction "P10_10") (pintype "bidirectional"))
      (node (ref "U$63") (pin "5") (pinfunction "A02_5") (pintype "bidirectional"))
      (node (ref "U$63") (pin "6") (pinfunction "A02-2_6") (pintype "bidirectional"))
    )
    (net (code "75") (name "/PUMP15_H") (class "Default")
      (node (ref "U$122") (pin "11") (pinfunction "P11_11") (pintype "bidirectional"))
      (node (ref "U$63") (pin "11") (pinfunction "BO1_11") (pintype "bidirectional"))
      (node (ref "U$63") (pin "12") (pinfunction "BO1-2_12") (pintype "bidirectional"))
    )
    (net (code "76") (name "/PUMP15_L") (class "Default")
      (node (ref "U$122") (pin "12") (pinfunction "P12_12") (pintype "bidirectional"))
      (node (ref "U$63") (pin "7") (pinfunction "BO2_7") (pintype "bidirectional"))
      (node (ref "U$63") (pin "8") (pinfunction "BO2-2_8") (pintype "bidirectional"))
    )
    (net (code "77") (name "/PUMP16_H") (class "Default")
      (node (ref "U$122") (pin "13") (pinfunction "P13_13") (pintype "bidirectional"))
      (node (ref "U$67") (pin "1") (pinfunction "AO1_1") (pintype "bidirectional"))
      (node (ref "U$67") (pin "2") (pinfunction "AO1-2_2") (pintype "bidirectional"))
    )
    (net (code "78") (name "/PUMP16_L") (class "Default")
      (node (ref "U$122") (pin "14") (pinfunction "P14_14") (pintype "bidirectional"))
      (node (ref "U$67") (pin "5") (pinfunction "A02_5") (pintype "bidirectional"))
      (node (ref "U$67") (pin "6") (pinfunction "A02-2_6") (pintype "bidirectional"))
    )
    (net (code "79") (name "/PUMP17_H") (class "Default")
      (node (ref "U$122") (pin "15") (pinfunction "P15_15") (pintype "bidirectional"))
      (node (ref "U$67") (pin "11") (pinfunction "BO1_11") (pintype "bidirectional"))
      (node (ref "U$67") (pin "12") (pinfunction "BO1-2_12") (pintype "bidirectional"))
    )
    (net (code "80") (name "/PUMP17_L") (class "Default")
      (node (ref "U$122") (pin "16") (pinfunction "P16_16") (pintype "bidirectional"))
      (node (ref "U$67") (pin "7") (pinfunction "BO2_7") (pintype "bidirectional"))
      (node (ref "U$67") (pin "8") (pinfunction "BO2-2_8") (pintype "bidirectional"))
    )
    (net (code "81") (name "/PUMP18_H") (class "Default")
      (node (ref "U$122") (pin "17") (pinfunction "P17_17") (pintype "bidirectional"))
      (node (ref "U$71") (pin "1") (pinfunction "AO1_1") (pintype "bidirectional"))
      (node (ref "U$71") (pin "2") (pinfunction "AO1-2_2") (pintype "bidirectional"))
    )
    (net (code "82") (name "/PUMP18_L") (class "Default")
      (node (ref "U$122") (pin "18") (pinfunction "P18_18") (pintype "bidirectional"))
      (node (ref "U$71") (pin "5") (pinfunction "A02_5") (pintype "bidirectional"))
      (node (ref "U$71") (pin "6") (pinfunction "A02-2_6") (pintype "bidirectional"))
    )
    (net (code "83") (name "/PUMP19_H") (class "Default")
      (node (ref "U$122") (pin "19") (pinfunction "P19_19") (pintype "bidirectional"))
      (node (ref "U$71") (pin "11") (pinfunction "BO1_11") (pintype "bidirectional"))
      (node (ref "U$71") (pin "12") (pinfunction "BO1-2_12") (pintype "bidirectional"))
    )
    (net (code "84") (name "/PUMP19_L") (class "Default")
      (node (ref "U$122") (pin "20") (pinfunction "P20_20") (pintype "bidirectional"))
      (node (ref "U$71") (pin "7") (pinfunction "BO2_7") (pintype "bidirectional"))
      (node (ref "U$71") (pin "8") (pinfunction "BO2-2_8") (pintype "bidirectional"))
    )
    (net (code "85") (name "/PWM0") (class "Default")
      (node (ref "U$29") (pin "6") (pinfunction "LED0_6") (pintype "bidirectional"))
      (node (ref "U$35") (pin "23") (pinfunction "PWMA_23") (pintype "bidirectional"))
    )
    (net (code "86") (name "/PWM1") (class "Default")
      (node (ref "U$29") (pin "7") (pinfunction "LED1_7") (pintype "bidirectional"))
      (node (ref "U$35") (pin "15") (pinfunction "PWMB_15") (pintype "bidirectional"))
    )
    (net (code "87") (name "/PWM2") (class "Default")
      (node (ref "U$29") (pin "8") (pinfunction "LED2_8") (pintype "bidirectional"))
      (node (ref "U$36") (pin "23") (pinfunction "PWMA_23") (pintype "bidirectional"))
    )
    (net (code "88") (name "/PWM3") (class "Default")
      (node (ref "U$29") (pin "9") (pinfunction "LED3_9") (pintype "bidirectional"))
      (node (ref "U$36") (pin "15") (pinfunction "PWMB_15") (pintype "bidirectional"))
    )
    (net (code "89") (name "/PWM4") (class "Default")
      (node (ref "U$29") (pin "10") (pinfunction "LED4_10") (pintype "bidirectional"))
      (node (ref "U$43") (pin "23") (pinfunction "PWMA_23") (pintype "bidirectional"))
    )
    (net (code "90") (name "/PWM5") (class "Default")
      (node (ref "U$29") (pin "11") (pinfunction "LED5_11") (pintype "bidirectional"))
      (node (ref "U$43") (pin "15") (pinfunction "PWMB_15") (pintype "bidirectional"))
    )
    (net (code "91") (name "/PWM6") (class "Default")
      (node (ref "U$29") (pin "12") (pinfunction "LED6_12") (pintype "bidirectional"))
      (node (ref "U$47") (pin "23") (pinfunction "PWMA_23") (pintype "bidirectional"))
    )
    (net (code "92") (name "/PWM7") (class "Default")
      (node (ref "U$29") (pin "13") (pinfunction "LED7_13") (pintype "bidirectional"))
      (node (ref "U$47") (pin "15") (pinfunction "PWMB_15") (pintype "bidirectional"))
    )
    (net (code "93") (name "/PWM8") (class "Default")
      (node (ref "U$29") (pin "15") (pinfunction "LED8_15") (pintype "bidirectional"))
      (node (ref "U$51") (pin "23") (pinfunction "PWMA_23") (pintype "bidirectional"))
    )
    (net (code "94") (name "/PWM9") (class "Default")
      (node (ref "U$29") (pin "16") (pinfunction "LED9_16") (pintype "bidirectional"))
      (node (ref "U$51") (pin "15") (pinfunction "PWMB_15") (pintype "bidirectional"))
    )
    (net (code "95") (name "/PWM10") (class "Default")
      (node (ref "U$29") (pin "17") (pinfunction "LED10_17") (pintype "bidirectional"))
      (node (ref "U$55") (pin "23") (pinfunction "PWMA_23") (pintype "bidirectional"))
    )
    (net (code "96") (name "/PWM11") (class "Default")
      (node (ref "U$29") (pin "18") (pinfunction "LED11_18") (pintype "bidirectional"))
      (node (ref "U$55") (pin "15") (pinfunction "PWMB_15") (pintype "bidirectional"))
    )
    (net (code "97") (name "/PWM12") (class "Default")
      (node (ref "U$29") (pin "19") (pinfunction "LED12_19") (pintype "bidirectional"))
      (node (ref "U$59") (pin "23") (pinfunction "PWMA_23") (pintype "bidirectional"))
    )
    (net (code "98") (name "/PWM13") (class "Default")
      (node (ref "U$29") (pin "20") (pinfunction "LED13_20") (pintype "bidirectional"))
      (node (ref "U$59") (pin "15") (pinfunction "PWMB_15") (pintype "bidirectional"))
    )
    (net (code "99") (name "/PWM14") (class "Default")
      (node (ref "U$29") (pin "21") (pinfunction "LED14_21") (pintype "bidirectional"))
      (node (ref "U$63") (pin "23") (pinfunction "PWMA_23") (pintype "bidirectional"))
    )
    (net (code "100") (name "/PWM15") (class "Default")
      (node (ref "U$29") (pin "22") (pinfunction "LED15_22") (pintype "bidirectional"))
      (node (ref "U$63") (pin "15") (pinfunction "PWMB_15") (pintype "bidirectional"))
    )
    (net (code "101") (name "/PWM16") (class "Default")
      (node (ref "U$30") (pin "6") (pinfunction "LED0_6") (pintype "bidirectional"))
      (node (ref "U$67") (pin "23") (pinfunction "PWMA_23") (pintype "bidirectional"))
    )
    (net (code "102") (name "/PWM17") (class "Default")
      (node (ref "U$30") (pin "7") (pinfunction "LED1_7") (pintype "bidirectional"))
      (node (ref "U$67") (pin "15") (pinfunction "PWMB_15") (pintype "bidirectional"))
    )
    (net (code "103") (name "/PWM18") (class "Default")
      (node (ref "U$30") (pin "8") (pinfunction "LED2_8") (pintype "bidirectional"))
      (node (ref "U$71") (pin "23") (pinfunction "PWMA_23") (pintype "bidirectional"))
    )
    (net (code "104") (name "/PWM19") (class "Default")
      (node (ref "U$30") (pin "9") (pinfunction "LED3_9") (pintype "bidirectional"))
      (node (ref "U$71") (pin "15") (pinfunction "PWMB_15") (pintype "bidirectional"))
    )
    (net (code "105") (name "/PWM_V0") (class "Default")
      (node (ref "U$30") (pin "10") (pinfunction "LED4_10") (pintype "bidirectional"))
      (node (ref "U$75") (pin "23") (pinfunction "PWMA_23") (pintype "bidirectional"))
    )
    (net (code "106") (name "/PWM_V1") (class "Default")
      (node (ref "U$30") (pin "11") (pinfunction "LED5_11") (pintype "bidirectional"))
      (node (ref "U$75") (pin "15") (pinfunction "PWMB_15") (pintype "bidirectional"))
    )
    (net (code "107") (name "/PWM_V2") (class "Default")
      (node (ref "U$30") (pin "12") (pinfunction "LED6_12") (pintype "bidirectional"))
      (node (ref "U$79") (pin "23") (pinfunction "PWMA_23") (pintype "bidirectional"))
    )
    (net (code "108") (name "/PWM_V3") (class "Default")
      (node (ref "U$30") (pin "13") (pinfunction "LED7_13") (pintype "bidirectional"))
      (node (ref "U$79") (pin "15") (pinfunction "PWMB_15") (pintype "bidirectional"))
    )
    (net (code "109") (name "/PWM_V4") (class "Default")
      (node (ref "U$30") (pin "15") (pinfunction "LED8_15") (pintype "bidirectional"))
      (node (ref "U$83") (pin "23") (pinfunction "PWMA_23") (pintype "bidirectional"))
    )
    (net (code "110") (name "/PWM_V5") (class "Default")
      (node (ref "U$30") (pin "16") (pinfunction "LED9_16") (pintype "bidirectional"))
      (node (ref "U$83") (pin "15") (pinfunction "PWMB_15") (pintype "bidirectional"))
    )
    (net (code "111") (name "/PWM_V6") (class "Default")
      (node (ref "U$30") (pin "17") (pinfunction "LED10_17") (pintype "bidirectional"))
      (node (ref "U$87") (pin "23") (pinfunction "PWMA_23") (pintype "bidirectional"))
    )
    (net (code "112") (name "/PWM_V7") (class "Default")
      (node (ref "U$30") (pin "18") (pinfunction "LED11_18") (pintype "bidirectional"))
      (node (ref "U$87") (pin "15") (pinfunction "PWMB_15") (pintype "bidirectional"))
    )
    (net (code "113") (name "/PWM_V8") (class "Default")
      (node (ref "U$30") (pin "19") (pinfunction "LED12_19") (pintype "bidirectional"))
      (node (ref "U$91") (pin "23") (pinfunction "PWMA_23") (pintype "bidirectional"))
    )
    (net (code "114") (name "/PWM_V9") (class "Default")
      (node (ref "U$30") (pin "20") (pinfunction "LED13_20") (pintype "bidirectional"))
      (node (ref "U$91") (pin "15") (pinfunction "PWMB_15") (pintype "bidirectional"))
    )
    (net (code "115") (name "/RESET") (class "Default")
      (node (ref "J2") (pin "4") (pinfunction "4_4") (pintype "bidirectional"))
      (node (ref "U$1") (pin "7") (pinfunction "NRST_7") (pintype "bidirectional"))
      (node (ref "U$130") (pin "2") (pinfunction "2_2") (pintype "bidirectional"))
      (node (ref "U$26") (pin "2") (pinfunction "2_2") (pintype "bidirectional"))
      (node (ref "U$28") (pin "1") (pinfunction "1_1") (pintype "bidirectional"))
    )
    (net (code "116") (name "/S0") (class "Default")
      (node (ref "U$115") (pin "4") (pinfunction "IO0_0_4") (pintype "bidirectional"))
      (node (ref "U$95") (pin "SS") (pinfunction "SS_SS") (pintype "bidirectional"))
    )
    (net (code "117") (name "/S1") (class "Default")
      (node (ref "U$115") (pin "5") (pinfunction "IO0_1_5") (pintype "bidirectional"))
      (node (ref "U$96") (pin "SS") (pinfunction "SS_SS") (pintype "bidirectional"))
    )
    (net (code "118") (name "/S2") (class "Default")
      (node (ref "U$115") (pin "6") (pinfunction "IO0_2_6") (pintype "bidirectional"))
      (node (ref "U$99") (pin "SS") (pinfunction "SS_SS") (pintype "bidirectional"))
    )
    (net (code "119") (name "/S3") (class "Default")
      (node (ref "U$101") (pin "SS") (pinfunction "SS_SS") (pintype "bidirectional"))
      (node (ref "U$115") (pin "7") (pinfunction "IO0_3_7") (pintype "bidirectional"))
    )
    (net (code "120") (name "/S4") (class "Default")
      (node (ref "U$103") (pin "SS") (pinfunction "SS_SS") (pintype "bidirectional"))
      (node (ref "U$115") (pin "8") (pinfunction "IO0_4_8") (pintype "bidirectional"))
    )
    (net (code "121") (name "/S5") (class "Default")
      (node (ref "U$105") (pin "SS") (pinfunction "SS_SS") (pintype "bidirectional"))
      (node (ref "U$115") (pin "9") (pinfunction "IO0_5_9") (pintype "bidirectional"))
    )
    (net (code "122") (name "/S6") (class "Default")
      (node (ref "U$107") (pin "SS") (pinfunction "SS_SS") (pintype "bidirectional"))
      (node (ref "U$115") (pin "10") (pinfunction "IO0_6_10") (pintype "bidirectional"))
    )
    (net (code "123") (name "/S7") (class "Default")
      (node (ref "U$109") (pin "SS") (pinfunction "SS_SS") (pintype "bidirectional"))
      (node (ref "U$115") (pin "11") (pinfunction "IO0_7_11") (pintype "bidirectional"))
    )
    (net (code "124") (name "/S8") (class "Default")
      (node (ref "U$111") (pin "SS") (pinfunction "SS_SS") (pintype "bidirectional"))
      (node (ref "U$115") (pin "13") (pinfunction "IO1_0_13") (pintype "bidirectional"))
    )
    (net (code "125") (name "/S9") (class "Default")
      (node (ref "U$113") (pin "SS") (pinfunction "SS_SS") (pintype "bidirectional"))
      (node (ref "U$115") (pin "14") (pinfunction "IO1_1_14") (pintype "bidirectional"))
    )
    (net (code "126") (name "/SPI1_MISO") (class "Default")
      (node (ref "J2") (pin "10") (pinfunction "10_10") (pintype "bidirectional"))
      (node (ref "U$1") (pin "16") (pinfunction "PA6_16") (pintype "bidirectional"))
      (node (ref "U$101") (pin "MISO") (pinfunction "MISO_MISO") (pintype "bidirectional"))
      (node (ref "U$103") (pin "MISO") (pinfunction "MISO_MISO") (pintype "bidirectional"))
      (node (ref "U$105") (pin "MISO") (pinfunction "MISO_MISO") (pintype "bidirectional"))
      (node (ref "U$107") (pin "MISO") (pinfunction "MISO_MISO") (pintype "bidirectional"))
      (node (ref "U$109") (pin "MISO") (pinfunction "MISO_MISO") (pintype "bidirectional"))
      (node (ref "U$111") (pin "MISO") (pinfunction "MISO_MISO") (pintype "bidirectional"))
      (node (ref "U$113") (pin "MISO") (pinfunction "MISO_MISO") (pintype "bidirectional"))
      (node (ref "U$95") (pin "MISO") (pinfunction "MISO_MISO") (pintype "bidirectional"))
      (node (ref "U$96") (pin "MISO") (pinfunction "MISO_MISO") (pintype "bidirectional"))
      (node (ref "U$99") (pin "MISO") (pinfunction "MISO_MISO") (pintype "bidirectional"))
    )
    (net (code "127") (name "/SPI1_SCK") (class "Default")
      (node (ref "J2") (pin "11") (pinfunction "11_11") (pintype "bidirectional"))
      (node (ref "U$1") (pin "15") (pinfunction "PA5_15") (pintype "bidirectional"))
      (node (ref "U$101") (pin "SCLK") (pinfunction "SCLK_SCLK") (pintype "bidirectional"))
      (node (ref "U$103") (pin "SCLK") (pinfunction "SCLK_SCLK") (pintype "bidirectional"))
      (node (ref "U$105") (pin "SCLK") (pinfunction "SCLK_SCLK") (pintype "bidirectional"))
      (node (ref "U$107") (pin "SCLK") (pinfunction "SCLK_SCLK") (pintype "bidirectional"))
      (node (ref "U$109") (pin "SCLK") (pinfunction "SCLK_SCLK") (pintype "bidirectional"))
      (node (ref "U$111") (pin "SCLK") (pinfunction "SCLK_SCLK") (pintype "bidirectional"))
      (node (ref "U$113") (pin "SCLK") (pinfunction "SCLK_SCLK") (pintype "bidirectional"))
      (node (ref "U$95") (pin "SCLK") (pinfunction "SCLK_SCLK") (pintype "bidirectional"))
      (node (ref "U$96") (pin "SCLK") (pinfunction "SCLK_SCLK") (pintype "bidirectional"))
      (node (ref "U$99") (pin "SCLK") (pinfunction "SCLK_SCLK") (pintype "bidirectional"))
    )
    (net (code "128") (name "/SWCLK") (class "Default")
      (node (ref "U$1") (pin "37") (pinfunction "PA14_37") (pintype "bidirectional"))
    )
    (net (code "129") (name "/SWDIO") (class "Default")
      (node (ref "U$1") (pin "34") (pinfunction "PA13_34") (pintype "bidirectional"))
    )
    (net (code "130") (name "/U1RX") (class "Default")
      (node (ref "J1") (pin "7") (pinfunction "7_7") (pintype "bidirectional"))
      (node (ref "U$1") (pin "31") (pinfunction "PA10_31") (pintype "bidirectional"))
      (node (ref "U$20") (pin "2") (pinfunction "TXD_2") (pintype "bidirectional"))
    )
    (net (code "131") (name "/U1TX") (class "Default")
      (node (ref "J1") (pin "6") (pinfunction "6_6") (pintype "bidirectional"))
      (node (ref "U$1") (pin "30") (pinfunction "PA9_30") (pintype "bidirectional"))
      (node (ref "U$20") (pin "3") (pinfunction "RXD_3") (pintype "bidirectional"))
    )
    (net (code "132") (name "/USB_5V") (class "Default")
      (node (ref "U$18") (pin "1") (pinfunction "VBUS_1") (pintype "bidirectional"))
      (node (ref "U$19") (pin "2") (pinfunction "2_2") (pintype "bidirectional"))
    )
    (net (code "133") (name "/VALVE0_H") (class "Default")
      (node (ref "U$123") (pin "1") (pinfunction "P1_1") (pintype "bidirectional"))
      (node (ref "U$75") (pin "1") (pinfunction "AO1_1") (pintype "bidirectional"))
      (node (ref "U$75") (pin "2") (pinfunction "AO1-2_2") (pintype "bidirectional"))
    )
    (net (code "134") (name "/VALVE0_L") (class "Default")
      (node (ref "U$123") (pin "2") (pinfunction "P2_2") (pintype "bidirectional"))
      (node (ref "U$75") (pin "5") (pinfunction "A02_5") (pintype "bidirectional"))
      (node (ref "U$75") (pin "6") (pinfunction "A02-2_6") (pintype "bidirectional"))
    )
    (net (code "135") (name "/VALVE1_H") (class "Default")
      (node (ref "U$123") (pin "3") (pinfunction "P3_3") (pintype "bidirectional"))
      (node (ref "U$75") (pin "11") (pinfunction "BO1_11") (pintype "bidirectional"))
      (node (ref "U$75") (pin "12") (pinfunction "BO1-2_12") (pintype "bidirectional"))
    )
    (net (code "136") (name "/VALVE1_L") (class "Default")
      (node (ref "U$123") (pin "4") (pinfunction "P4_4") (pintype "bidirectional"))
      (node (ref "U$75") (pin "7") (pinfunction "BO2_7") (pintype "bidirectional"))
      (node (ref "U$75") (pin "8") (pinfunction "BO2-2_8") (pintype "bidirectional"))
    )
    (net (code "137") (name "/VALVE2_H") (class "Default")
      (node (ref "U$123") (pin "5") (pinfunction "P5_5") (pintype "bidirectional"))
      (node (ref "U$79") (pin "1") (pinfunction "AO1_1") (pintype "bidirectional"))
      (node (ref "U$79") (pin "2") (pinfunction "AO1-2_2") (pintype "bidirectional"))
    )
    (net (code "138") (name "/VALVE2_L") (class "Default")
      (node (ref "U$123") (pin "6") (pinfunction "P6_6") (pintype "bidirectional"))
      (node (ref "U$79") (pin "5") (pinfunction "A02_5") (pintype "bidirectional"))
      (node (ref "U$79") (pin "6") (pinfunction "A02-2_6") (pintype "bidirectional"))
    )
    (net (code "139") (name "/VALVE3_H") (class "Default")
      (node (ref "U$123") (pin "7") (pinfunction "P7_7") (pintype "bidirectional"))
      (node (ref "U$79") (pin "11") (pinfunction "BO1_11") (pintype "bidirectional"))
      (node (ref "U$79") (pin "12") (pinfunction "BO1-2_12") (pintype "bidirectional"))
    )
    (net (code "140") (name "/VALVE3_L") (class "Default")
      (node (ref "U$123") (pin "8") (pinfunction "P8_8") (pintype "bidirectional"))
      (node (ref "U$79") (pin "7") (pinfunction "BO2_7") (pintype "bidirectional"))
      (node (ref "U$79") (pin "8") (pinfunction "BO2-2_8") (pintype "bidirectional"))
    )
    (net (code "141") (name "/VALVE4_H") (class "Default")
      (node (ref "U$123") (pin "9") (pinfunction "P9_9") (pintype "bidirectional"))
      (node (ref "U$83") (pin "1") (pinfunction "AO1_1") (pintype "bidirectional"))
      (node (ref "U$83") (pin "2") (pinfunction "AO1-2_2") (pintype "bidirectional"))
    )
    (net (code "142") (name "/VALVE4_L") (class "Default")
      (node (ref "U$123") (pin "10") (pinfunction "P10_10") (pintype "bidirectional"))
      (node (ref "U$83") (pin "5") (pinfunction "A02_5") (pintype "bidirectional"))
      (node (ref "U$83") (pin "6") (pinfunction "A02-2_6") (pintype "bidirectional"))
    )
    (net (code "143") (name "/VALVE5_H") (class "Default")
      (node (ref "U$123") (pin "11") (pinfunction "P11_11") (pintype "bidirectional"))
      (node (ref "U$83") (pin "11") (pinfunction "BO1_11") (pintype "bidirectional"))
      (node (ref "U$83") (pin "12") (pinfunction "BO1-2_12") (pintype "bidirectional"))
    )
    (net (code "144") (name "/VALVE5_L") (class "Default")
      (node (ref "U$123") (pin "12") (pinfunction "P12_12") (pintype "bidirectional"))
      (node (ref "U$83") (pin "7") (pinfunction "BO2_7") (pintype "bidirectional"))
      (node (ref "U$83") (pin "8") (pinfunction "BO2-2_8") (pintype "bidirectional"))
    )
    (net (code "145") (name "/VALVE6_H") (class "Default")
      (node (ref "U$123") (pin "13") (pinfunction "P13_13") (pintype "bidirectional"))
      (node (ref "U$87") (pin "1") (pinfunction "AO1_1") (pintype "bidirectional"))
      (node (ref "U$87") (pin "2") (pinfunction "AO1-2_2") (pintype "bidirectional"))
    )
    (net (code "146") (name "/VALVE6_L") (class "Default")
      (node (ref "U$123") (pin "14") (pinfunction "P14_14") (pintype "bidirectional"))
      (node (ref "U$87") (pin "5") (pinfunction "A02_5") (pintype "bidirectional"))
      (node (ref "U$87") (pin "6") (pinfunction "A02-2_6") (pintype "bidirectional"))
    )
    (net (code "147") (name "/VALVE7_H") (class "Default")
      (node (ref "U$123") (pin "15") (pinfunction "P15_15") (pintype "bidirectional"))
      (node (ref "U$87") (pin "11") (pinfunction "BO1_11") (pintype "bidirectional"))
      (node (ref "U$87") (pin "12") (pinfunction "BO1-2_12") (pintype "bidirectional"))
    )
    (net (code "148") (name "/VALVE7_L") (class "Default")
      (node (ref "U$123") (pin "16") (pinfunction "P16_16") (pintype "bidirectional"))
      (node (ref "U$87") (pin "7") (pinfunction "BO2_7") (pintype "bidirectional"))
      (node (ref "U$87") (pin "8") (pinfunction "BO2-2_8") (pintype "bidirectional"))
    )
    (net (code "149") (name "/VALVE8_H") (class "Default")
      (node (ref "U$123") (pin "17") (pinfunction "P17_17") (pintype "bidirectional"))
      (node (ref "U$91") (pin "1") (pinfunction "AO1_1") (pintype "bidirectional"))
      (node (ref "U$91") (pin "2") (pinfunction "AO1-2_2") (pintype "bidirectional"))
    )
    (net (code "150") (name "/VALVE8_L") (class "Default")
      (node (ref "U$123") (pin "18") (pinfunction "P18_18") (pintype "bidirectional"))
      (node (ref "U$91") (pin "5") (pinfunction "A02_5") (pintype "bidirectional"))
      (node (ref "U$91") (pin "6") (pinfunction "A02-2_6") (pintype "bidirectional"))
    )
    (net (code "151") (name "/VALVE9_H") (class "Default")
      (node (ref "U$123") (pin "19") (pinfunction "P19_19") (pintype "bidirectional"))
      (node (ref "U$91") (pin "11") (pinfunction "BO1_11") (pintype "bidirectional"))
      (node (ref "U$91") (pin "12") (pinfunction "BO1-2_12") (pintype "bidirectional"))
    )
    (net (code "152") (name "/VALVE9_L") (class "Default")
      (node (ref "U$123") (pin "20") (pinfunction "P20_20") (pintype "bidirectional"))
      (node (ref "U$91") (pin "7") (pinfunction "BO2_7") (pintype "bidirectional"))
      (node (ref "U$91") (pin "8") (pinfunction "BO2-2_8") (pintype "bidirectional"))
    )
    (net (code "153") (name "/VBAT") (class "Default")
      (node (ref "J2") (pin "20") (pinfunction "20_20") (pintype "bidirectional"))
    )
    (net (code "154") (name "/VCC") (class "Default")
      (node (ref "J1") (pin "20") (pinfunction "20_20") (pintype "bidirectional"))
      (node (ref "J2") (pin "3") (pinfunction "3_3") (pintype "bidirectional"))
      (node (ref "U$1") (pin "1") (pinfunction "VBAT_1") (pintype "bidirectional"))
      (node (ref "U$1") (pin "24") (pinfunction "VDD_1_24") (pintype "bidirectional"))
      (node (ref "U$1") (pin "36") (pinfunction "VDD_2_36") (pintype "bidirectional"))
      (node (ref "U$1") (pin "48") (pinfunction "VDD_3_48") (pintype "bidirectional"))
      (node (ref "U$1") (pin "9") (pinfunction "VDDA_9") (pintype "bidirectional"))
      (node (ref "U$100") (pin "2") (pinfunction "2_2") (pintype "bidirectional"))
      (node (ref "U$101") (pin "VSUP") (pinfunction "VSUP_VSUP") (pintype "bidirectional"))
      (node (ref "U$102") (pin "2") (pinfunction "2_2") (pintype "bidirectional"))
      (node (ref "U$103") (pin "VSUP") (pinfunction "VSUP_VSUP") (pintype "bidirectional"))
      (node (ref "U$104") (pin "2") (pinfunction "2_2") (pintype "bidirectional"))
      (node (ref "U$105") (pin "VSUP") (pinfunction "VSUP_VSUP") (pintype "bidirectional"))
      (node (ref "U$106") (pin "2") (pinfunction "2_2") (pintype "bidirectional"))
      (node (ref "U$107") (pin "VSUP") (pinfunction "VSUP_VSUP") (pintype "bidirectional"))
      (node (ref "U$108") (pin "2") (pinfunction "2_2") (pintype "bidirectional"))
      (node (ref "U$109") (pin "VSUP") (pinfunction "VSUP_VSUP") (pintype "bidirectional"))
      (node (ref "U$110") (pin "2") (pinfunction "2_2") (pintype "bidirectional"))
      (node (ref "U$111") (pin "VSUP") (pinfunction "VSUP_VSUP") (pintype "bidirectional"))
      (node (ref "U$112") (pin "2") (pinfunction "2_2") (pintype "bidirectional"))
      (node (ref "U$113") (pin "VSUP") (pinfunction "VSUP_VSUP") (pintype "bidirectional"))
      (node (ref "U$114") (pin "2") (pinfunction "2_2") (pintype "bidirectional"))
      (node (ref "U$115") (pin "24") (pinfunction "VDD_24") (pintype "bidirectional"))
      (node (ref "U$116") (pin "2") (pinfunction "2_2") (pintype "bidirectional"))
      (node (ref "U$12") (pin "1") (pinfunction "1_1") (pintype "bidirectional"))
      (node (ref "U$124") (pin "2") (pinfunction "VCC_2") (pintype "bidirectional"))
      (node (ref "U$125") (pin "2") (pinfunction "VCC_2") (pintype "bidirectional"))
      (node (ref "U$128") (pin "2") (pinfunction "2_2") (pintype "bidirectional"))
      (node (ref "U$129") (pin "2") (pinfunction "2_2") (pintype "bidirectional"))
      (node (ref "U$13") (pin "2") (pinfunction "2_2") (pintype "bidirectional"))
      (node (ref "U$14") (pin "2") (pinfunction "2_2") (pintype "bidirectional"))
      (node (ref "U$15") (pin "2") (pinfunction "2_2") (pintype "bidirectional"))
      (node (ref "U$16") (pin "2") (pinfunction "2_2") (pintype "bidirectional"))
      (node (ref "U$17") (pin "2") (pinfunction "2_2") (pintype "bidirectional"))
      (node (ref "U$20") (pin "16") (pinfunction "VCC_16") (pintype "bidirectional"))
      (node (ref "U$20") (pin "4") (pinfunction "V3_4") (pintype "bidirectional"))
      (node (ref "U$21") (pin "2") (pinfunction "2_2") (pintype "bidirectional"))
      (node (ref "U$22") (pin "1") (pinfunction "1_1") (pintype "bidirectional"))
      (node (ref "U$23") (pin "1") (pinfunction "1_1") (pintype "bidirectional"))
      (node (ref "U$28") (pin "2") (pinfunction "2_2") (pintype "bidirectional"))
      (node (ref "U$29") (pin "28") (pinfunction "VDD_28") (pintype "bidirectional"))
      (node (ref "U$29") (pin "4") (pinfunction "A3_4") (pintype "bidirectional"))
      (node (ref "U$30") (pin "28") (pinfunction "VDD_28") (pintype "bidirectional"))
      (node (ref "U$30") (pin "3") (pinfunction "A2_3") (pintype "bidirectional"))
      (node (ref "U$32") (pin "1") (pinfunction "1_1") (pintype "bidirectional"))
      (node (ref "U$33") (pin "1") (pinfunction "1_1") (pintype "bidirectional"))
      (node (ref "U$35") (pin "17") (pinfunction "BIN1_17") (pintype "bidirectional"))
      (node (ref "U$35") (pin "19") (pinfunction "STBY_19") (pintype "bidirectional"))
      (node (ref "U$35") (pin "20") (pinfunction "VCC_20") (pintype "bidirectional"))
      (node (ref "U$35") (pin "21") (pinfunction "AIN1_21") (pintype "bidirectional"))
      (node (ref "U$36") (pin "17") (pinfunction "BIN1_17") (pintype "bidirectional"))
      (node (ref "U$36") (pin "19") (pinfunction "STBY_19") (pintype "bidirectional"))
      (node (ref "U$36") (pin "20") (pinfunction "VCC_20") (pintype "bidirectional"))
      (node (ref "U$36") (pin "21") (pinfunction "AIN1_21") (pintype "bidirectional"))
      (node (ref "U$39") (pin "2") (pinfunction "2_2") (pintype "bidirectional"))
      (node (ref "U$42") (pin "2") (pinfunction "2_2") (pintype "bidirectional"))
      (node (ref "U$43") (pin "17") (pinfunction "BIN1_17") (pintype "bidirectional"))
      (node (ref "U$43") (pin "19") (pinfunction "STBY_19") (pintype "bidirectional"))
      (node (ref "U$43") (pin "20") (pinfunction "VCC_20") (pintype "bidirectional"))
      (node (ref "U$43") (pin "21") (pinfunction "AIN1_21") (pintype "bidirectional"))
      (node (ref "U$46") (pin "2") (pinfunction "2_2") (pintype "bidirectional"))
      (node (ref "U$47") (pin "17") (pinfunction "BIN1_17") (pintype "bidirectional"))
      (node (ref "U$47") (pin "19") (pinfunction "STBY_19") (pintype "bidirectional"))
      (node (ref "U$47") (pin "20") (pinfunction "VCC_20") (pintype "bidirectional"))
      (node (ref "U$47") (pin "21") (pinfunction "AIN1_21") (pintype "bidirectional"))
      (node (ref "U$50") (pin "2") (pinfunction "2_2") (pintype "bidirectional"))
      (node (ref "U$51") (pin "17") (pinfunction "BIN1_17") (pintype "bidirectional"))
      (node (ref "U$51") (pin "19") (pinfunction "STBY_19") (pintype "bidirectional"))
      (node (ref "U$51") (pin "20") (pinfunction "VCC_20") (pintype "bidirectional"))
      (node (ref "U$51") (pin "21") (pinfunction "AIN1_21") (pintype "bidirectional"))
      (node (ref "U$54") (pin "2") (pinfunction "2_2") (pintype "bidirectional"))
      (node (ref "U$55") (pin "17") (pinfunction "BIN1_17") (pintype "bidirectional"))
      (node (ref "U$55") (pin "19") (pinfunction "STBY_19") (pintype "bidirectional"))
      (node (ref "U$55") (pin "20") (pinfunction "VCC_20") (pintype "bidirectional"))
      (node (ref "U$55") (pin "21") (pinfunction "AIN1_21") (pintype "bidirectional"))
      (node (ref "U$58") (pin "2") (pinfunction "2_2") (pintype "bidirectional"))
      (node (ref "U$59") (pin "17") (pinfunction "BIN1_17") (pintype "bidirectional"))
      (node (ref "U$59") (pin "19") (pinfunction "STBY_19") (pintype "bidirectional"))
      (node (ref "U$59") (pin "20") (pinfunction "VCC_20") (pintype "bidirectional"))
      (node (ref "U$59") (pin "21") (pinfunction "AIN1_21") (pintype "bidirectional"))
      (node (ref "U$62") (pin "2") (pinfunction "2_2") (pintype "bidirectional"))
      (node (ref "U$63") (pin "17") (pinfunction "BIN1_17") (pintype "bidirectional"))
      (node (ref "U$63") (pin "19") (pinfunction "STBY_19") (pintype "bidirectional"))
      (node (ref "U$63") (pin "20") (pinfunction "VCC_20") (pintype "bidirectional"))
      (node (ref "U$63") (pin "21") (pinfunction "AIN1_21") (pintype "bidirectional"))
      (node (ref "U$66") (pin "2") (pinfunction "2_2") (pintype "bidirectional"))
      (node (ref "U$67") (pin "17") (pinfunction "BIN1_17") (pintype "bidirectional"))
      (node (ref "U$67") (pin "19") (pinfunction "STBY_19") (pintype "bidirectional"))
      (node (ref "U$67") (pin "20") (pinfunction "VCC_20") (pintype "bidirectional"))
      (node (ref "U$67") (pin "21") (pinfunction "AIN1_21") (pintype "bidirectional"))
      (node (ref "U$70") (pin "2") (pinfunction "2_2") (pintype "bidirectional"))
      (node (ref "U$71") (pin "17") (pinfunction "BIN1_17") (pintype "bidirectional"))
      (node (ref "U$71") (pin "19") (pinfunction "STBY_19") (pintype "bidirectional"))
      (node (ref "U$71") (pin "20") (pinfunction "VCC_20") (pintype "bidirectional"))
      (node (ref "U$71") (pin "21") (pinfunction "AIN1_21") (pintype "bidirectional"))
      (node (ref "U$74") (pin "2") (pinfunction "2_2") (pintype "bidirectional"))
      (node (ref "U$75") (pin "17") (pinfunction "BIN1_17") (pintype "bidirectional"))
      (node (ref "U$75") (pin "19") (pinfunction "STBY_19") (pintype "bidirectional"))
      (node (ref "U$75") (pin "20") (pinfunction "VCC_20") (pintype "bidirectional"))
      (node (ref "U$75") (pin "21") (pinfunction "AIN1_21") (pintype "bidirectional"))
      (node (ref "U$78") (pin "2") (pinfunction "2_2") (pintype "bidirectional"))
      (node (ref "U$79") (pin "17") (pinfunction "BIN1_17") (pintype "bidirectional"))
      (node (ref "U$79") (pin "19") (pinfunction "STBY_19") (pintype "bidirectional"))
      (node (ref "U$79") (pin "20") (pinfunction "VCC_20") (pintype "bidirectional"))
      (node (ref "U$79") (pin "21") (pinfunction "AIN1_21") (pintype "bidirectional"))
      (node (ref "U$82") (pin "2") (pinfunction "2_2") (pintype "bidirectional"))
      (node (ref "U$83") (pin "17") (pinfunction "BIN1_17") (pintype "bidirectional"))
      (node (ref "U$83") (pin "19") (pinfunction "STBY_19") (pintype "bidirectional"))
      (node (ref "U$83") (pin "20") (pinfunction "VCC_20") (pintype "bidirectional"))
      (node (ref "U$83") (pin "21") (pinfunction "AIN1_21") (pintype "bidirectional"))
      (node (ref "U$86") (pin "2") (pinfunction "2_2") (pintype "bidirectional"))
      (node (ref "U$87") (pin "17") (pinfunction "BIN1_17") (pintype "bidirectional"))
      (node (ref "U$87") (pin "19") (pinfunction "STBY_19") (pintype "bidirectional"))
      (node (ref "U$87") (pin "20") (pinfunction "VCC_20") (pintype "bidirectional"))
      (node (ref "U$87") (pin "21") (pinfunction "AIN1_21") (pintype "bidirectional"))
      (node (ref "U$9") (pin "2") (pinfunction "VOUT_2") (pintype "bidirectional"))
      (node (ref "U$9") (pin "4") (pinfunction "VOUT2_4") (pintype "bidirectional"))
      (node (ref "U$90") (pin "2") (pinfunction "2_2") (pintype "bidirectional"))
      (node (ref "U$91") (pin "17") (pinfunction "BIN1_17") (pintype "bidirectional"))
      (node (ref "U$91") (pin "19") (pinfunction "STBY_19") (pintype "bidirectional"))
      (node (ref "U$91") (pin "20") (pinfunction "VCC_20") (pintype "bidirectional"))
      (node (ref "U$91") (pin "21") (pinfunction "AIN1_21") (pintype "bidirectional"))
      (node (ref "U$94") (pin "2") (pinfunction "2_2") (pintype "bidirectional"))
      (node (ref "U$95") (pin "VSUP") (pinfunction "VSUP_VSUP") (pintype "bidirectional"))
      (node (ref "U$96") (pin "VSUP") (pinfunction "VSUP_VSUP") (pintype "bidirectional"))
      (node (ref "U$97") (pin "2") (pinfunction "2_2") (pintype "bidirectional"))
      (node (ref "U$98") (pin "2") (pinfunction "2_2") (pintype "bidirectional"))
      (node (ref "U$99") (pin "VSUP") (pinfunction "VSUP_VSUP") (pintype "bidirectional"))
    )
    (net (code "155") (name "Net-(U$124-GND)") (class "Default")
      (node (ref "U$124") (pin "1") (pinfunction "GND_1") (pintype "bidirectional"))
      (node (ref "U$126") (pin "1") (pinfunction "1_1") (pintype "bidirectional"))
    )
    (net (code "156") (name "Net-(U$125-GND)") (class "Default")
      (node (ref "U$125") (pin "1") (pinfunction "GND_1") (pintype "bidirectional"))
      (node (ref "U$127") (pin "1") (pinfunction "1_1") (pintype "bidirectional"))
    )
    (net (code "157") (name "unconnected-(U$20-CTS#-Pad9)") (class "Default")
      (node (ref "U$20") (pin "9") (pinfunction "CTS#_9") (pintype "bidirectional"))
    )
    (net (code "158") (name "unconnected-(U$20-DCD#-Pad12)") (class "Default")
      (node (ref "U$20") (pin "12") (pinfunction "DCD#_12") (pintype "bidirectional"))
    )
    (net (code "159") (name "unconnected-(U$20-DSR#-Pad10)") (class "Default")
      (node (ref "U$20") (pin "10") (pinfunction "DSR#_10") (pintype "bidirectional"))
    )
    (net (code "160") (name "unconnected-(U$20-DTR#-Pad13)") (class "Default")
      (node (ref "U$20") (pin "13") (pinfunction "DTR#_13") (pintype "bidirectional"))
    )
    (net (code "161") (name "unconnected-(U$20-NC.-Pad7)") (class "Default")
      (node (ref "U$20") (pin "7") (pinfunction "NC._7") (pintype "bidirectional"))
    )
    (net (code "162") (name "unconnected-(U$20-NC.2-Pad8)") (class "Default")
      (node (ref "U$20") (pin "8") (pinfunction "NC.2_8") (pintype "bidirectional"))
    )
    (net (code "163") (name "unconnected-(U$20-R232-Pad15)") (class "Default")
      (node (ref "U$20") (pin "15") (pinfunction "R232_15") (pintype "bidirectional"))
    )
    (net (code "164") (name "unconnected-(U$20-RI#-Pad11)") (class "Default")
      (node (ref "U$20") (pin "11") (pinfunction "RI#_11") (pintype "bidirectional"))
    )
    (net (code "165") (name "unconnected-(U$20-RTS#-Pad14)") (class "Default")
      (node (ref "U$20") (pin "14") (pinfunction "RTS#_14") (pintype "bidirectional"))
    )
    (net (code "166") (name "unconnected-(U$30-LED14-Pad21)") (class "Default")
      (node (ref "U$30") (pin "21") (pinfunction "LED14_21") (pintype "bidirectional"))
    )
    (net (code "167") (name "unconnected-(U$30-LED15-Pad22)") (class "Default")
      (node (ref "U$30") (pin "22") (pinfunction "LED15_22") (pintype "bidirectional"))
    )
    (net (code "168") (name "unconnected-(U$95-PadNC)") (class "Default")
      (node (ref "U$95") (pin "NC") (pinfunction "NC_NC") (pintype "bidirectional"))
    )
    (net (code "169") (name "unconnected-(U$96-PadNC)") (class "Default")
      (node (ref "U$96") (pin "NC") (pinfunction "NC_NC") (pintype "bidirectional"))
    )
    (net (code "170") (name "unconnected-(U$99-PadNC)") (class "Default")
      (node (ref "U$99") (pin "NC") (pinfunction "NC_NC") (pintype "bidirectional"))
    )
    (net (code "171") (name "unconnected-(U$101-PadNC)") (class "Default")
      (node (ref "U$101") (pin "NC") (pinfunction "NC_NC") (pintype "bidirectional"))
    )
    (net (code "172") (name "unconnected-(U$103-PadNC)") (class "Default")
      (node (ref "U$103") (pin "NC") (pinfunction "NC_NC") (pintype "bidirectional"))
    )
    (net (code "173") (name "unconnected-(U$105-PadNC)") (class "Default")
      (node (ref "U$105") (pin "NC") (pinfunction "NC_NC") (pintype "bidirectional"))
    )
    (net (code "174") (name "unconnected-(U$107-PadNC)") (class "Default")
      (node (ref "U$107") (pin "NC") (pinfunction "NC_NC") (pintype "bidirectional"))
    )
    (net (code "175") (name "unconnected-(U$109-PadNC)") (class "Default")
      (node (ref "U$109") (pin "NC") (pinfunction "NC_NC") (pintype "bidirectional"))
    )
    (net (code "176") (name "unconnected-(U$111-PadNC)") (class "Default")
      (node (ref "U$111") (pin "NC") (pinfunction "NC_NC") (pintype "bidirectional"))
    )
    (net (code "177") (name "unconnected-(U$113-PadNC)") (class "Default")
      (node (ref "U$113") (pin "NC") (pinfunction "NC_NC") (pintype "bidirectional"))
    )
    (net (code "178") (name "unconnected-(U$115-INT#-Pad1)") (class "Default")
      (node (ref "U$115") (pin "1") (pinfunction "INT#_1") (pintype "bidirectional"))
    )
    (net (code "179") (name "unconnected-(U$115-IO1_2-Pad15)") (class "Default")
      (node (ref "U$115") (pin "15") (pinfunction "IO1_2_15") (pintype "bidirectional"))
    )
    (net (code "180") (name "unconnected-(U$115-IO1_3-Pad16)") (class "Default")
      (node (ref "U$115") (pin "16") (pinfunction "IO1_3_16") (pintype "bidirectional"))
    )
    (net (code "181") (name "unconnected-(U$115-IO1_4-Pad17)") (class "Default")
      (node (ref "U$115") (pin "17") (pinfunction "IO1_4_17") (pintype "bidirectional"))
    )
    (net (code "182") (name "unconnected-(U$115-IO1_5-Pad18)") (class "Default")
      (node (ref "U$115") (pin "18") (pinfunction "IO1_5_18") (pintype "bidirectional"))
    )
    (net (code "183") (name "unconnected-(U$115-IO1_6-Pad19)") (class "Default")
      (node (ref "U$115") (pin "19") (pinfunction "IO1_6_19") (pintype "bidirectional"))
    )
    (net (code "184") (name "unconnected-(U$115-IO1_7-Pad20)") (class "Default")
      (node (ref "U$115") (pin "20") (pinfunction "IO1_7_20") (pintype "bidirectional"))
    )
    (net (code "185") (name "unconnected-(U$117-Pad3)") (class "Default")
      (node (ref "U$117") (pin "3") (pinfunction "3_3") (pintype "bidirectional"))
    )
    (net (code "186") (name "unconnected-(U$117-Pad4)") (class "Default")
      (node (ref "U$117") (pin "4") (pinfunction "4_4") (pintype "bidirectional"))
    )
    (net (code "187") (name "unconnected-(U$118-Pad3)") (class "Default")
      (node (ref "U$118") (pin "3") (pinfunction "3_3") (pintype "bidirectional"))
    )
    (net (code "188") (name "unconnected-(U$118-Pad4)") (class "Default")
      (node (ref "U$118") (pin "4") (pinfunction "4_4") (pintype "bidirectional"))
    )
  )
)
